# transponder-11_0_0.net
KiCad netlist of a schematic drawn in EAGLE
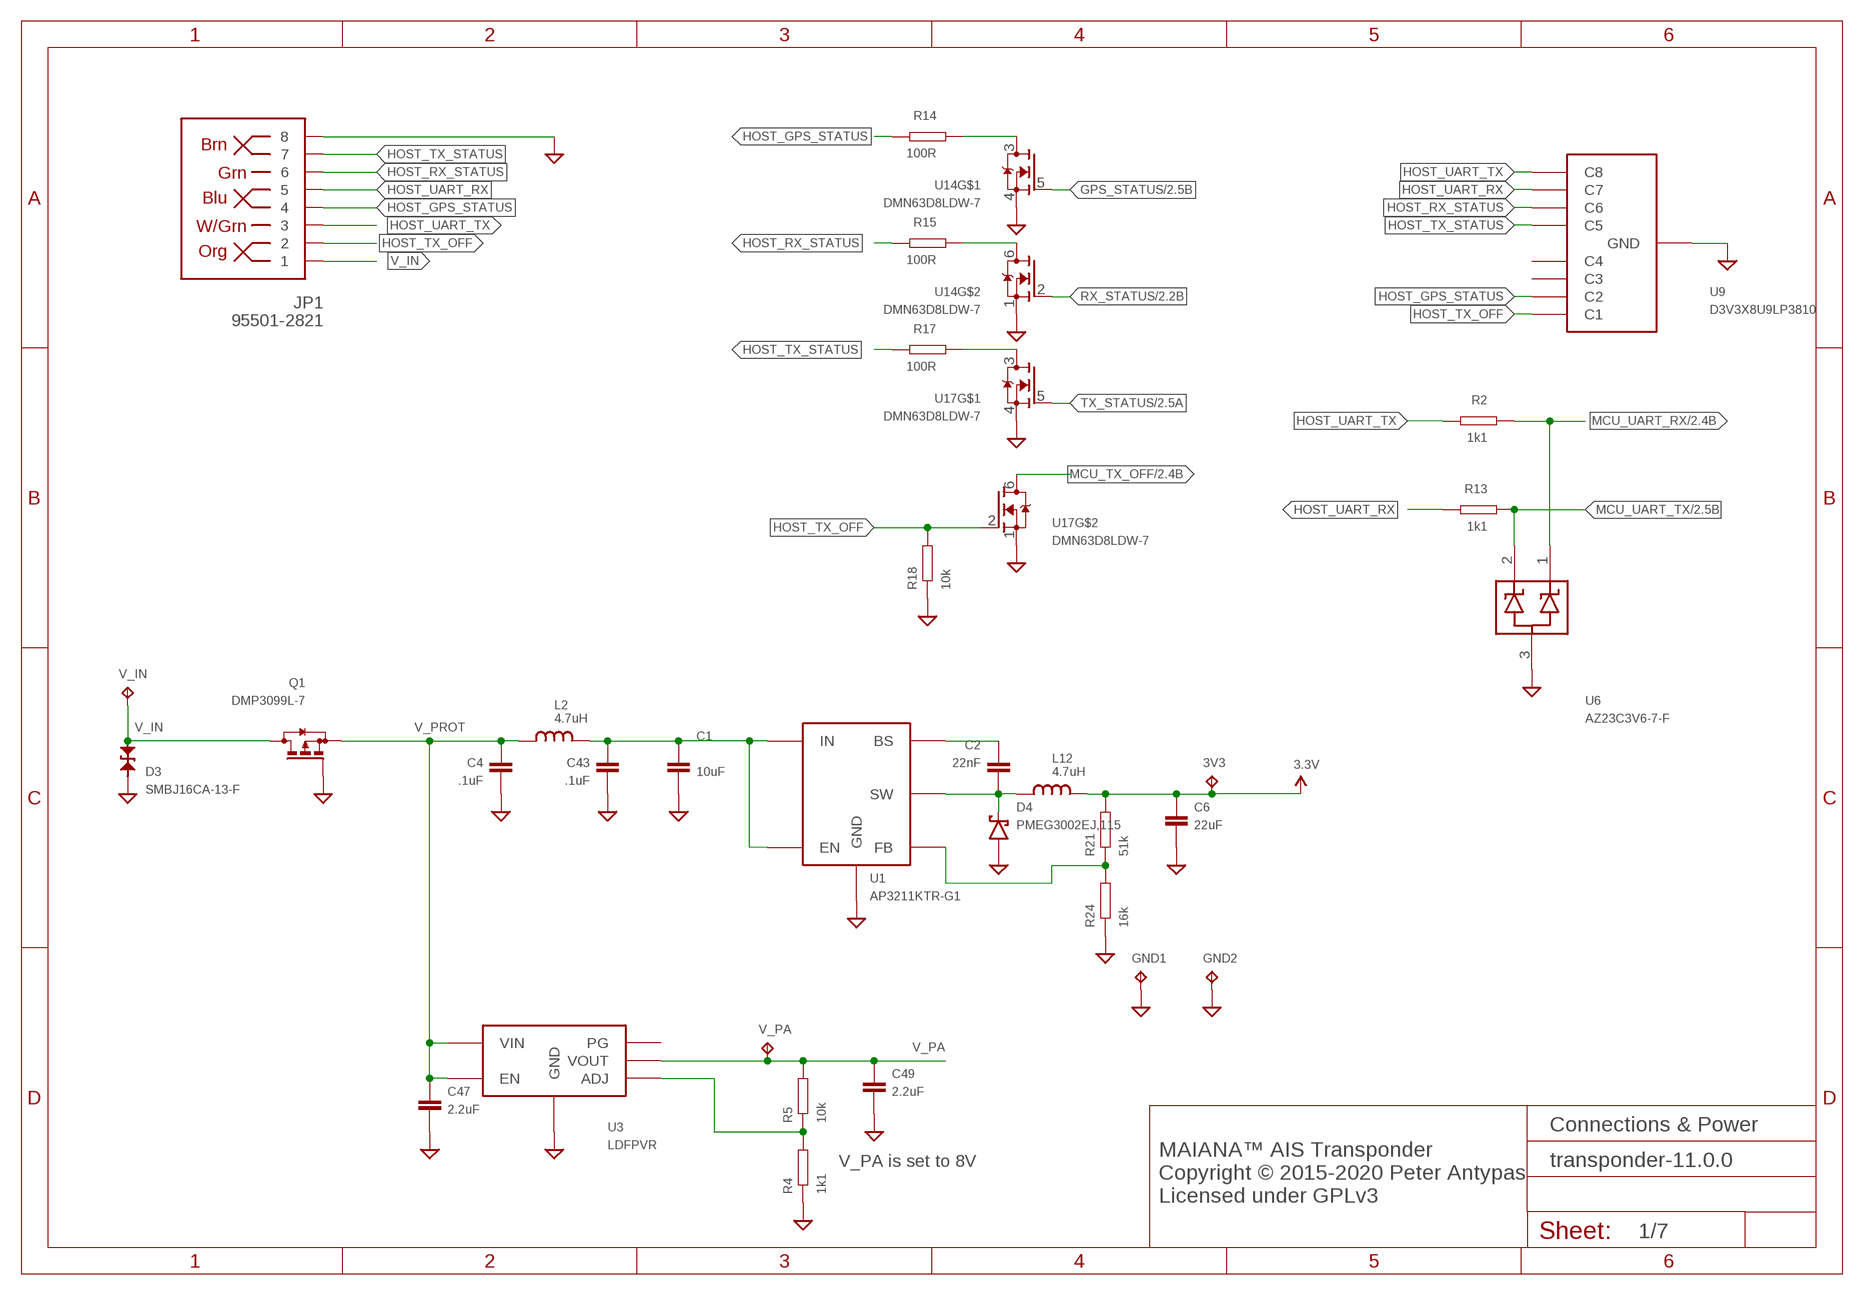
[diagram p0: schematic, sheet 1]
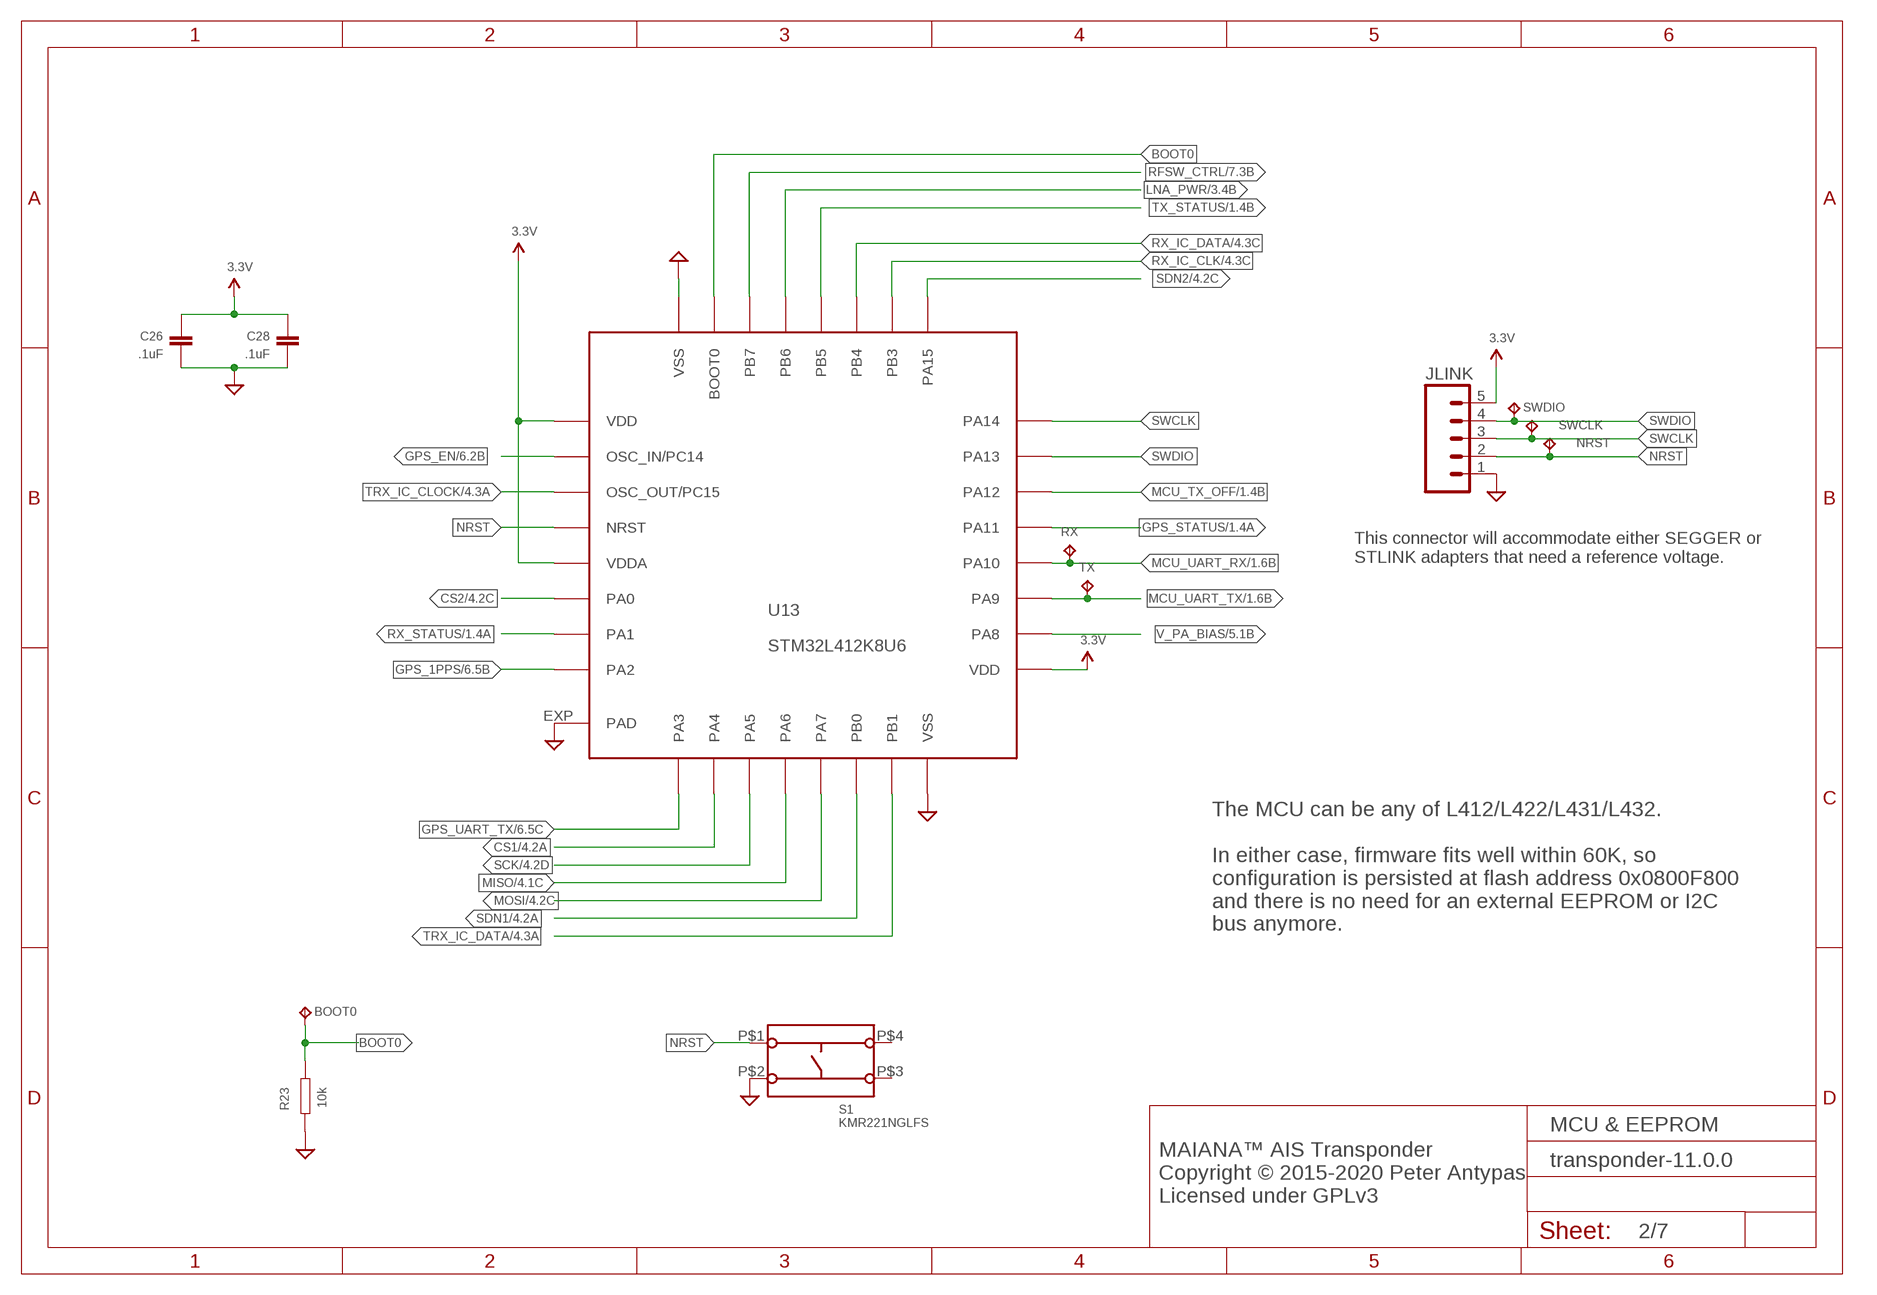
[diagram p1: schematic, sheet 2]
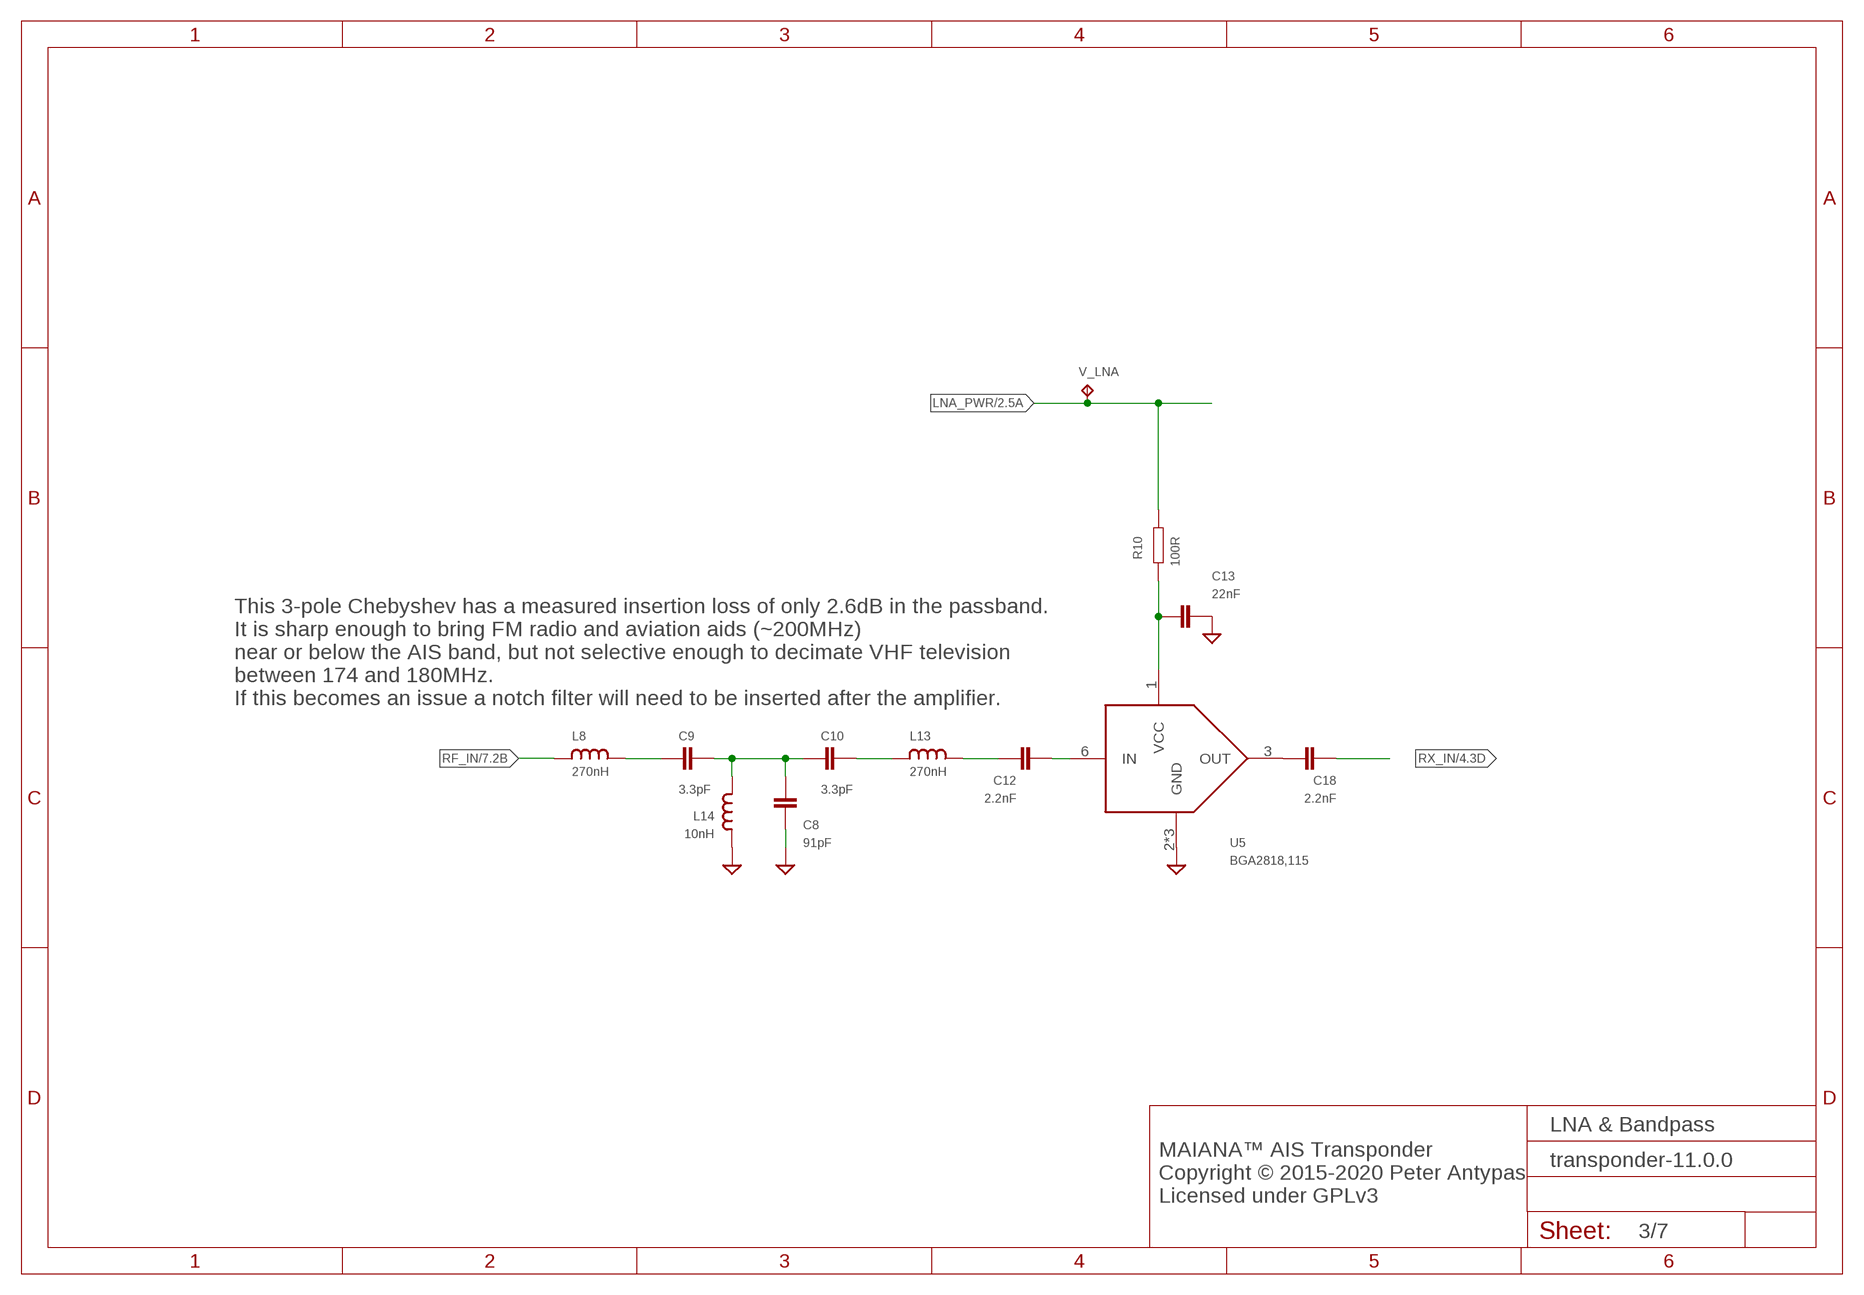
[diagram p2: schematic, sheet 3]
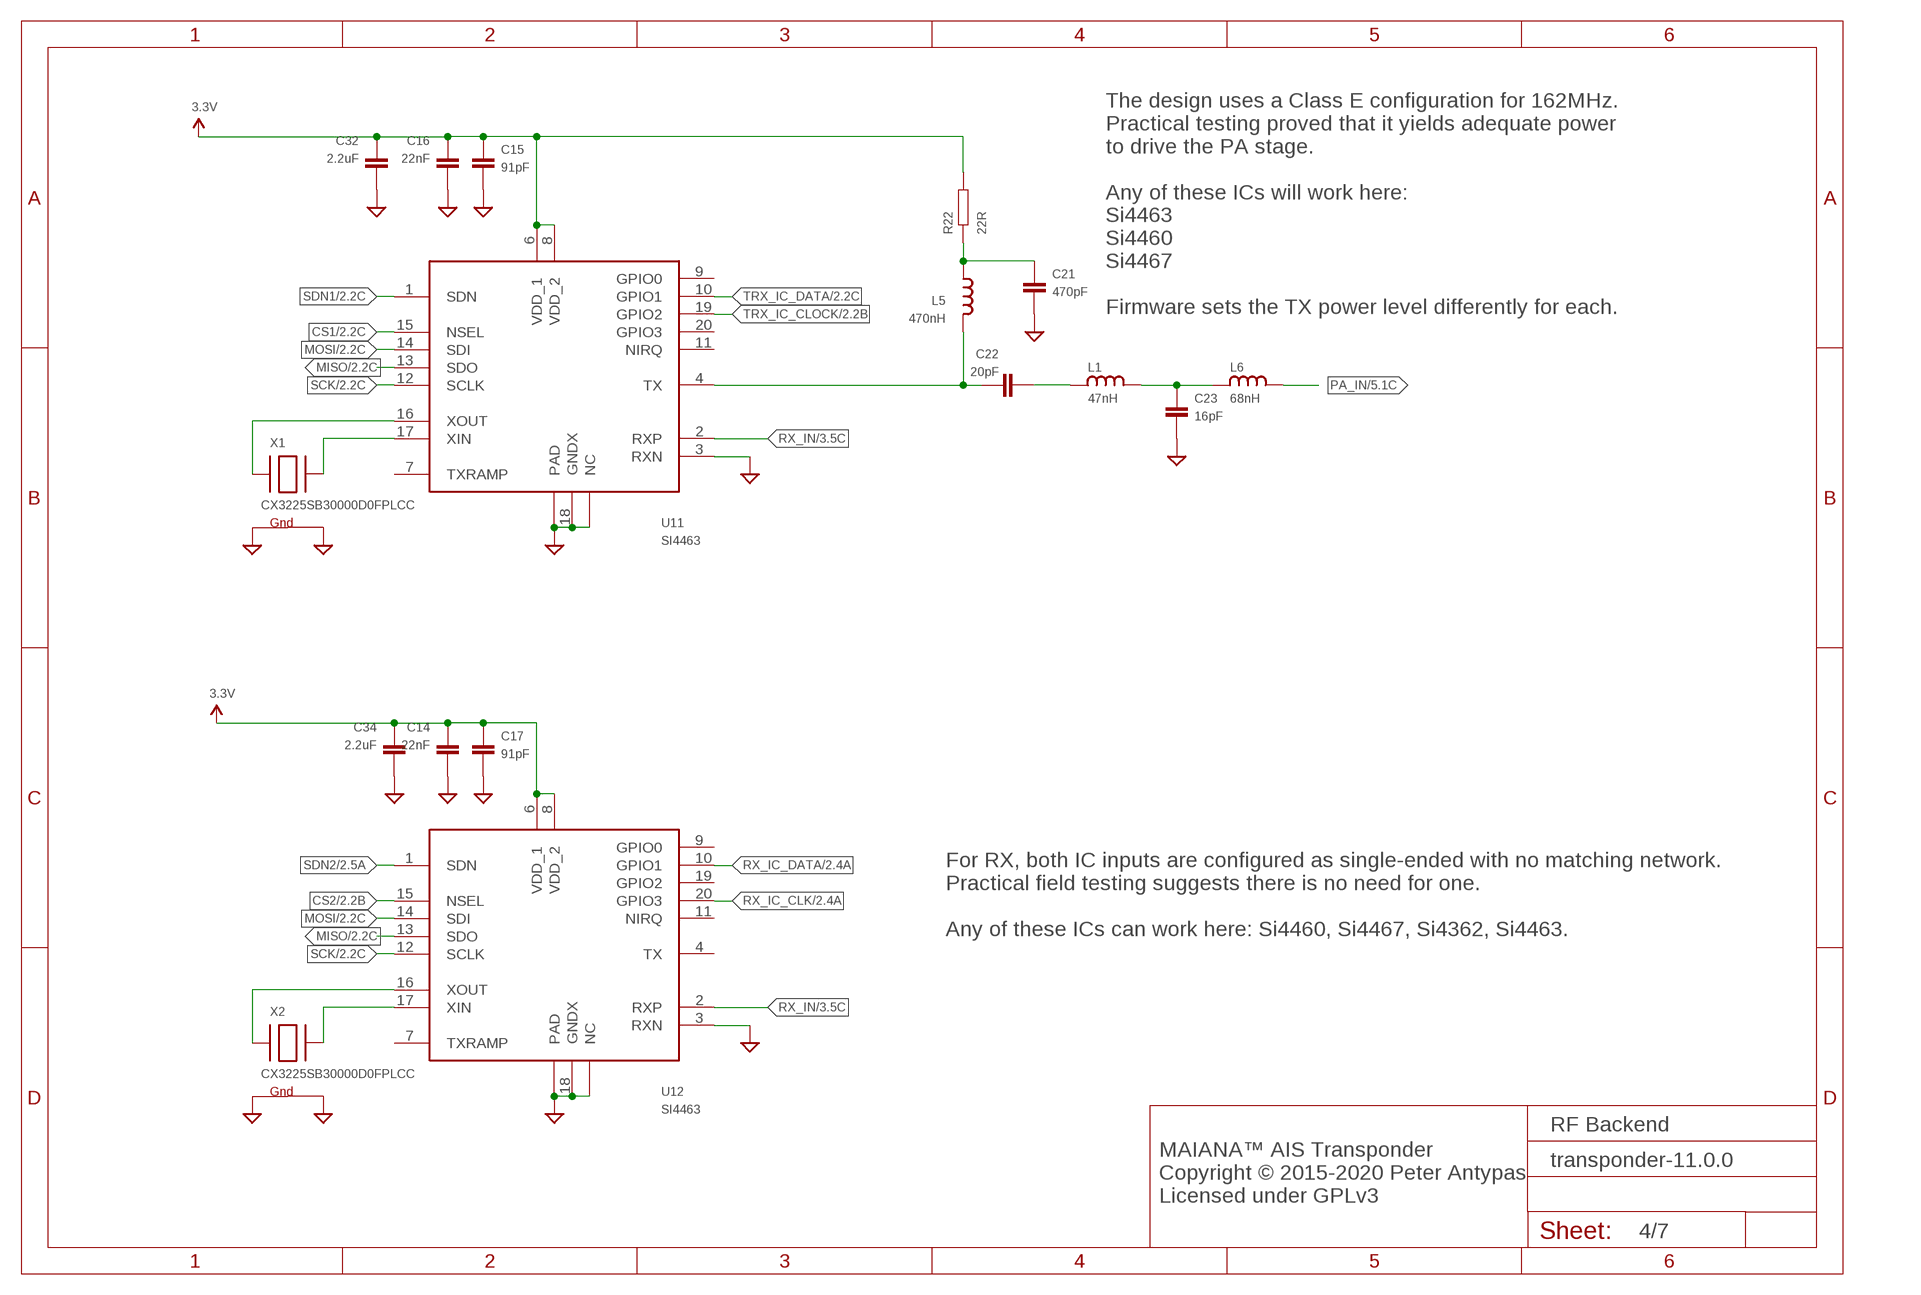
[diagram p3: schematic, sheet 4]
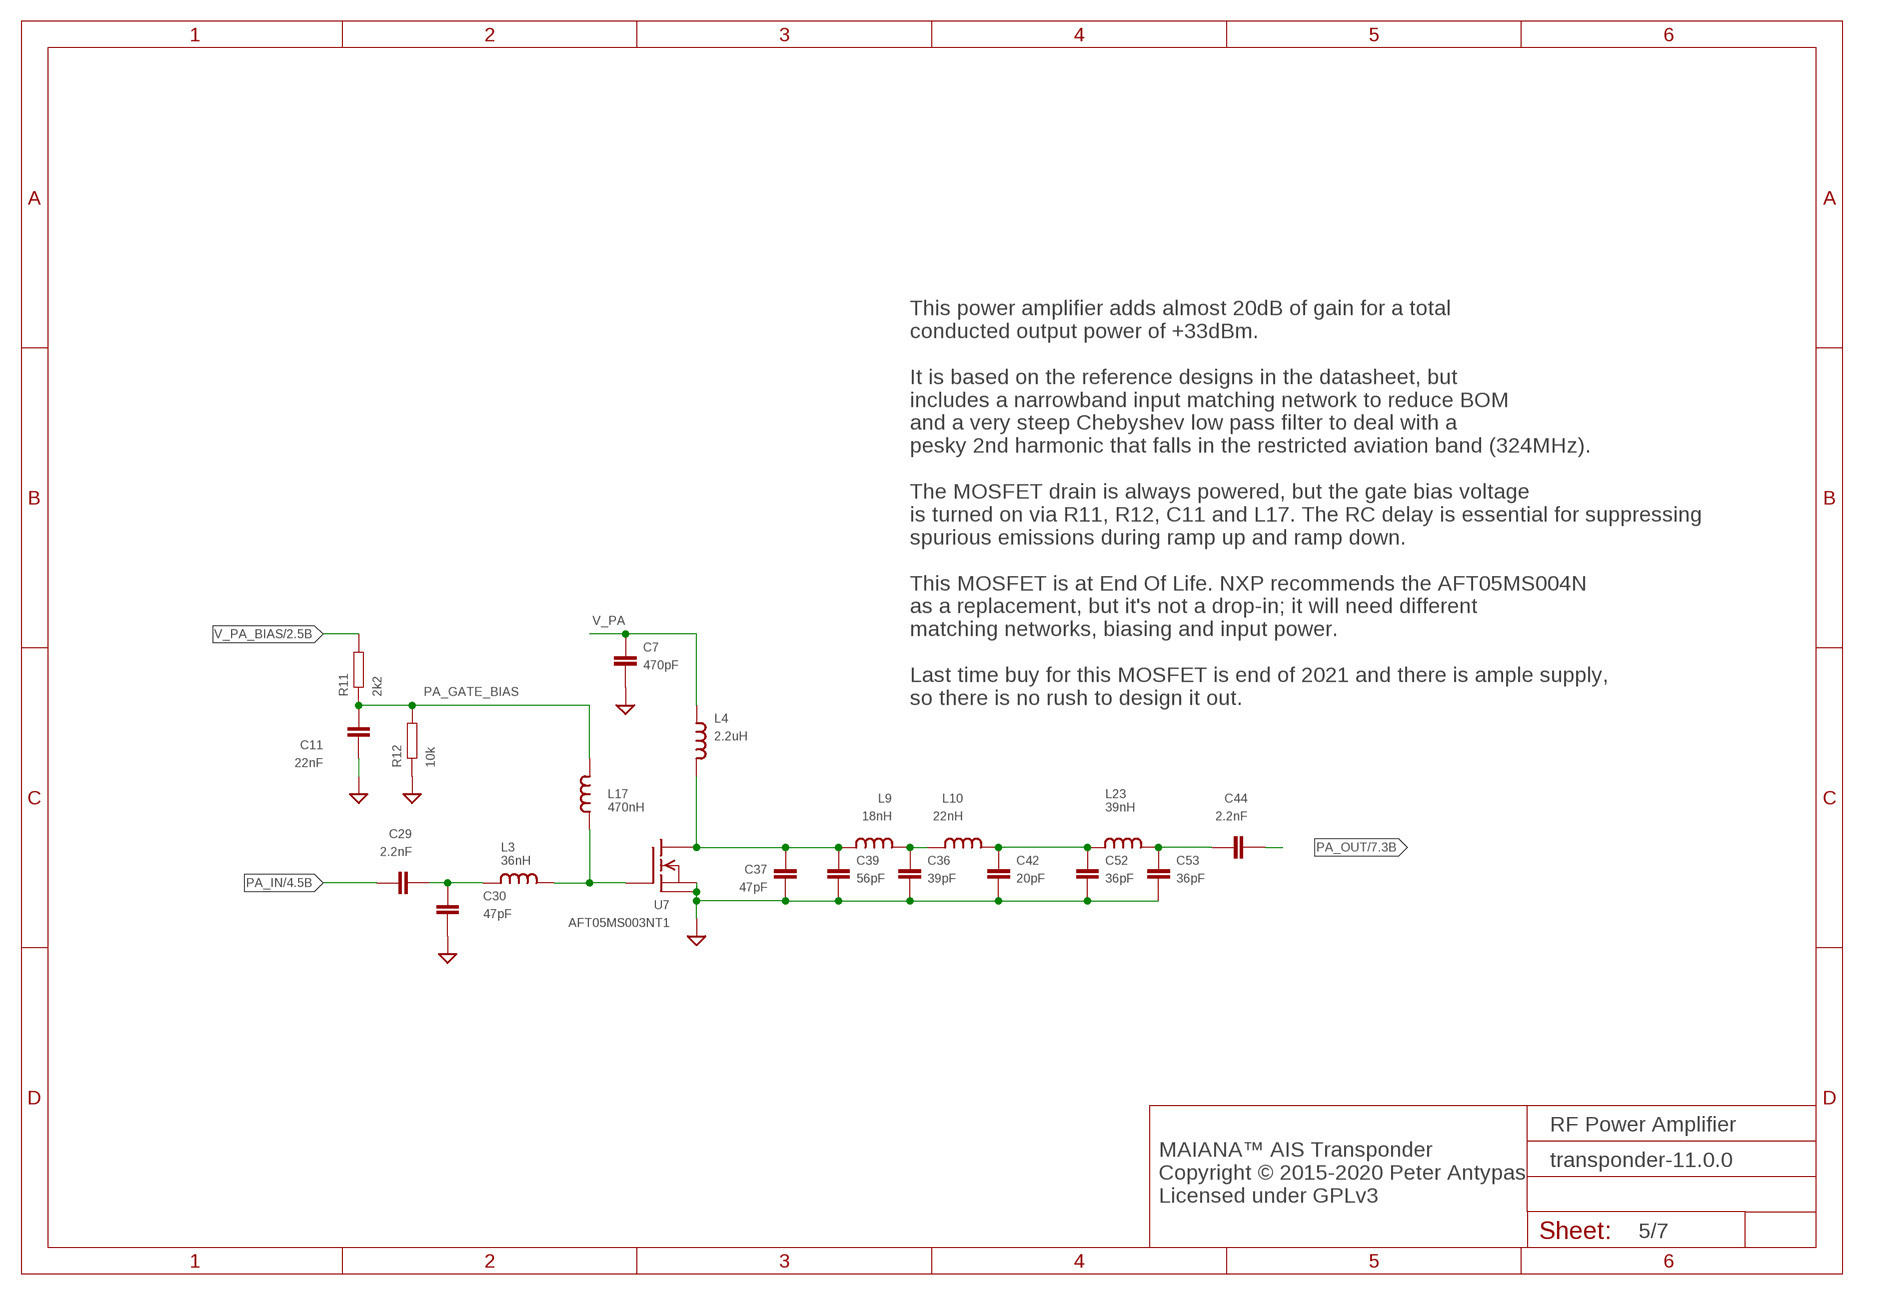
[diagram p4: schematic, sheet 5]
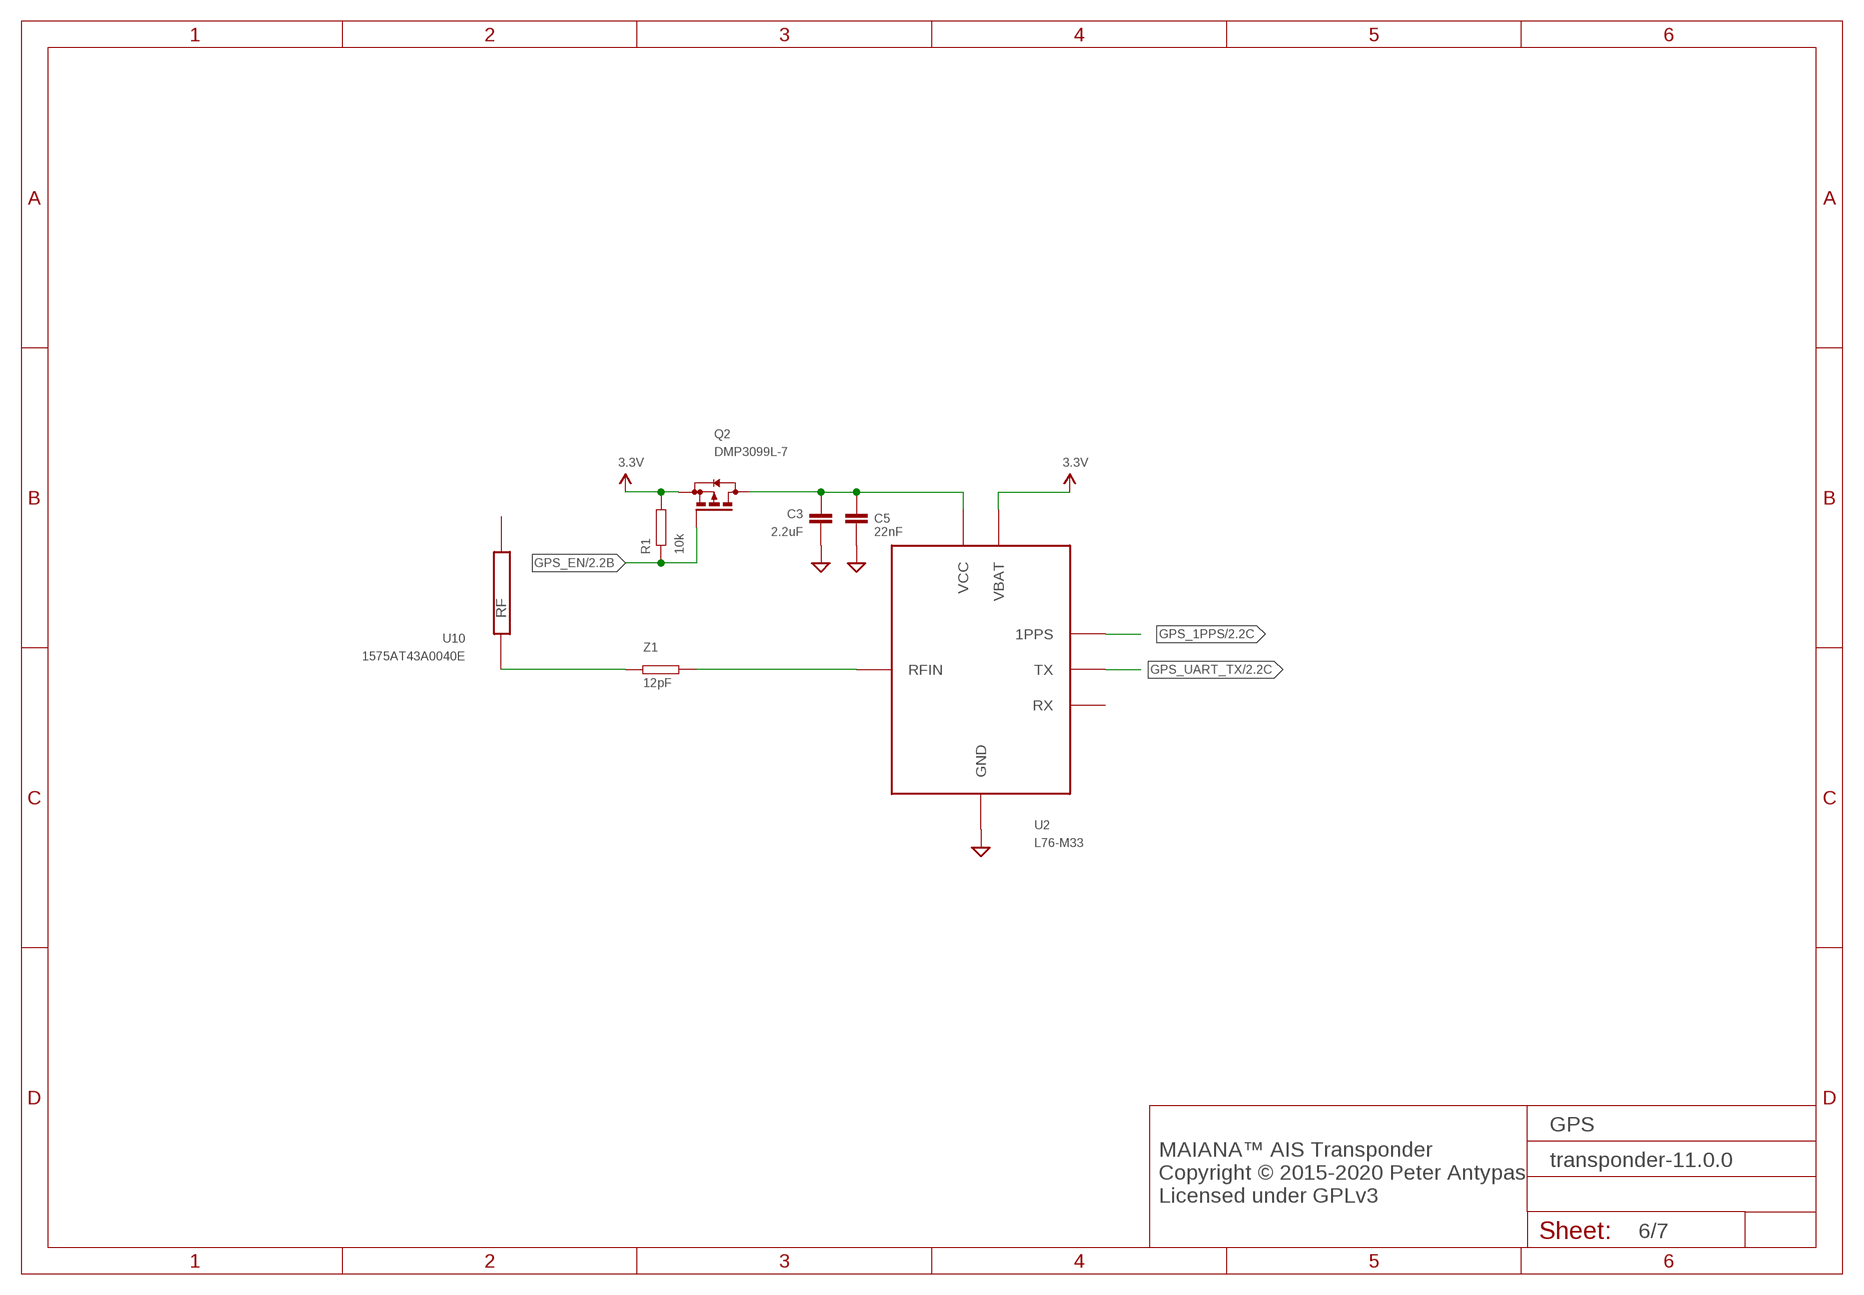
[diagram p5: schematic, sheet 6]
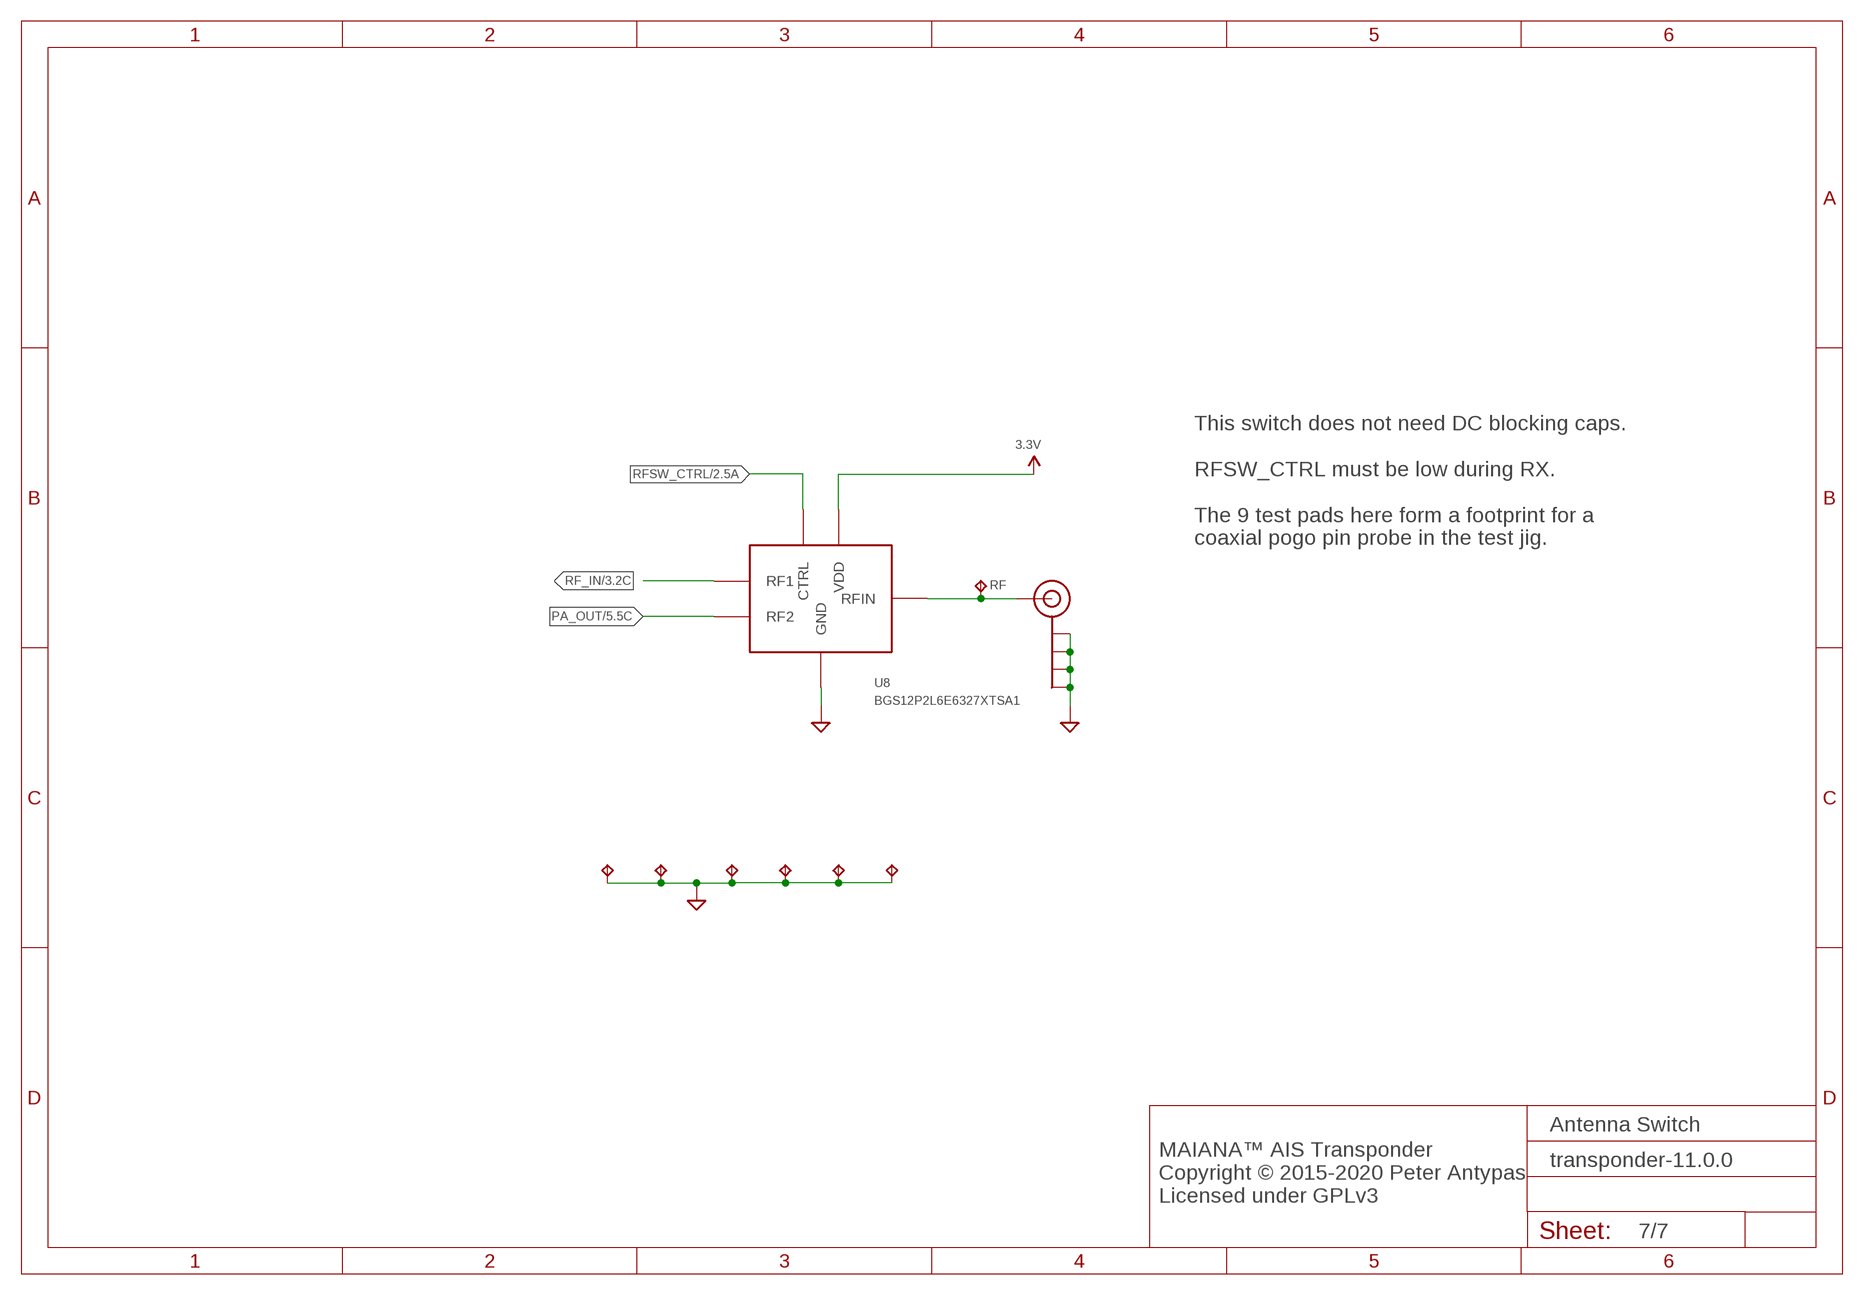
[diagram p6: schematic, sheet 7]

(export (version "E")
  (design (tool "Eeschema 10.0.6"))
  (components
    (comp (ref "C7")
      (value "470pF")
      (footprint "eagle-import:0603")
      (fields (field (name "PARTNO") "GRM1885C1H471JA01D"))
      (libsource (lib "eagle-import") (part "CAPACITOR0603"))
    )
    (comp (ref "C11")
      (value "22nF")
      (footprint "eagle-import:0603")
      (fields (field (name "PARTNO") "GRM188R71E223KA01D"))
      (libsource (lib "eagle-import") (part "CAPACITOR0603"))
    )
    (comp (ref "C29")
      (value "2.2nF")
      (footprint "eagle-import:0603")
      (fields (field (name "PARTNO") "GRM1885C1H222JA01J"))
      (libsource (lib "eagle-import") (part "CAPACITOR0603"))
    )
    (comp (ref "C30")
      (value "47pF")
      (footprint "eagle-import:0603")
      (fields (field (name "PARTNO") "GRM1885C1H470JA01J"))
      (libsource (lib "eagle-import") (part "CAPACITOR0603"))
    )
    (comp (ref "C36")
      (value "39pF")
      (footprint "eagle-import:0603")
      (fields (field (name "PARTNO") "GRM1885C1H390JA01D"))
      (libsource (lib "eagle-import") (part "CAPACITOR0603"))
    )
    (comp (ref "C37")
      (value "47pF")
      (footprint "eagle-import:0603")
      (fields (field (name "PARTNO") "GRM1885C1H470JA01J"))
      (libsource (lib "eagle-import") (part "CAPACITOR0603"))
    )
    (comp (ref "C39")
      (value "56pF")
      (footprint "eagle-import:0603")
      (fields (field (name "PARTNO") "GRM1885C1H560JA01D"))
      (libsource (lib "eagle-import") (part "CAPACITOR0603"))
    )
    (comp (ref "C42")
      (value "20pF")
      (footprint "eagle-import:0603")
      (fields (field (name "PARTNO") "GRM1885C1H200JA01D"))
      (libsource (lib "eagle-import") (part "CAPACITOR0603"))
    )
    (comp (ref "C44")
      (value "2.2nF")
      (footprint "eagle-import:0603")
      (fields (field (name "PARTNO") "GRM1885C1H222JA01J"))
      (libsource (lib "eagle-import") (part "CAPACITOR0603"))
    )
    (comp (ref "C52")
      (value "36pF")
      (footprint "eagle-import:0603")
      (fields (field (name "PARTNO") "06035A360JAT2A"))
      (libsource (lib "eagle-import") (part "CAPACITOR0603"))
    )
    (comp (ref "C53")
      (value "36pF")
      (footprint "eagle-import:0603")
      (fields (field (name "PARTNO") "06035A360JAT2A"))
      (libsource (lib "eagle-import") (part "CAPACITOR0603"))
    )
    (comp (ref "L3")
      (value "36nH")
      (footprint "eagle-import:0603")
      (fields (field (name "PARTNO") "LQW18AN36NG00D"))
      (libsource (lib "eagle-import") (part "INDUCTOR0603"))
    )
    (comp (ref "L4")
      (value "2.2uH")
      (footprint "eagle-import:0805")
      (fields (field (name "PARTNO") "BRC2012T2R2MD"))
      (libsource (lib "eagle-import") (part "INDUCTOR0805"))
    )
    (comp (ref "L9")
      (value "18nH")
      (footprint "eagle-import:0603")
      (fields (field (name "PARTNO") "LQW18AN18NG00D"))
      (libsource (lib "eagle-import") (part "INDUCTOR0603"))
    )
    (comp (ref "L10")
      (value "22nH")
      (footprint "eagle-import:0603")
      (fields (field (name "PARTNO") "LQW18AN22NJ00D"))
      (libsource (lib "eagle-import") (part "INDUCTOR0603"))
    )
    (comp (ref "L17")
      (value "470nH")
      (footprint "eagle-import:0603")
      (fields (field (name "PARTNO") "HK1608R47J-T"))
      (libsource (lib "eagle-import") (part "INDUCTOR0603"))
    )
    (comp (ref "L23")
      (value "39nH")
      (footprint "eagle-import:0603")
      (fields (field (name "PARTNO") "LQW18AN39NG00D"))
      (libsource (lib "eagle-import") (part "INDUCTOR0603"))
    )
    (comp (ref "R11")
      (value "2k2")
      (footprint "eagle-import:0603")
      (fields (field (name "PARTNO") "RC0603FR-072K2L"))
      (libsource (lib "eagle-import") (part "RESISTOR0603"))
    )
    (comp (ref "R12")
      (value "10k")
      (footprint "eagle-import:0603")
      (fields (field (name "PARTNO") "RC0603JR-0710KL"))
      (libsource (lib "eagle-import") (part "RESISTOR0603"))
    )
    (comp (ref "U7")
      (value "AFT05MS003NT1")
      (footprint "eagle-import:SOT-89")
      (libsource (lib "eagle-import") (part "AFT0SMS003N"))
    )
    (comp (ref "J$1")
      (value "SMA_EDGE")
      (footprint "eagle-import:SMA-EDGE")
      (libsource (lib "eagle-import") (part "SMA_EDGE"))
    )
    (comp (ref "RF")
      (value "TPTP10R")
      (footprint "eagle-import:TP10R")
      (libsource (lib "eagle-import") (part "TPTP10R"))
    )
    (comp (ref "SWDIO1")
      (value "TPTP12R")
      (footprint "eagle-import:TP12R")
      (libsource (lib "eagle-import") (part "TPTP12R"))
    )
    (comp (ref "SWDIO2")
      (value "TPTP12R")
      (footprint "eagle-import:TP12R")
      (libsource (lib "eagle-import") (part "TPTP12R"))
    )
    (comp (ref "SWDIO3")
      (value "TPTP12R")
      (footprint "eagle-import:TP12R")
      (libsource (lib "eagle-import") (part "TPTP12R"))
    )
    (comp (ref "SWDIO4")
      (value "TPTP12R")
      (footprint "eagle-import:TP12R")
      (libsource (lib "eagle-import") (part "TPTP12R"))
    )
    (comp (ref "SWDIO5")
      (value "TPTP12R")
      (footprint "eagle-import:TP12R")
      (libsource (lib "eagle-import") (part "TPTP12R"))
    )
    (comp (ref "SWDIO6")
      (value "TPTP12R")
      (footprint "eagle-import:TP12R")
      (libsource (lib "eagle-import") (part "TPTP12R"))
    )
    (comp (ref "U8")
      (value "BGS12P2L6E6327XTSA1")
      (footprint "eagle-import:PSON50P145X100X50-6N")
      (fields (field (name "PARTNO") "BGS12PL6") (field (name "PARTNO_1") "‎BGS12P2L6E6327XTSA1‎"))
      (libsource (lib "eagle-import") (part "BGS12PL6"))
    )
    (comp (ref "C3")
      (value "2.2uF")
      (footprint "eagle-import:0603")
      (fields (field (name "PARTNO") "EMK107BJ225KA-T"))
      (libsource (lib "eagle-import") (part "CAPACITOR0603"))
    )
    (comp (ref "C5")
      (value "22nF")
      (footprint "eagle-import:0603")
      (fields (field (name "PARTNO") "GRM188R71E223KA01D"))
      (libsource (lib "eagle-import") (part "CAPACITOR0603"))
    )
    (comp (ref "Q2")
      (value "DMP3099L-7")
      (footprint "eagle-import:SOT23")
      (libsource (lib "eagle-import") (part "BSS84"))
    )
    (comp (ref "R1")
      (value "10k")
      (footprint "eagle-import:0603")
      (fields (field (name "PARTNO") "RC0603JR-0710KL"))
      (libsource (lib "eagle-import") (part "RESISTOR0603"))
    )
    (comp (ref "U2")
      (value "L76-M33")
      (footprint "eagle-import:GPS_MODULE")
      (fields (field (name "PARTNO") "L70B-M39"))
      (libsource (lib "eagle-import") (part "L70"))
    )
    (comp (ref "U10")
      (value "1575AT43A0040E")
      (footprint "eagle-import:1575AT43A0040E")
      (libsource (lib "eagle-import") (part "1575AT43A0040E"))
    )
    (comp (ref "Z1")
      (value "12pF")
      (footprint "eagle-import:0603")
      (fields (field (name "PARTNO") "‎GRM1885C1H120GA01D‎"))
      (libsource (lib "eagle-import") (part "RESISTOR0603"))
    )
    (comp (ref "3V3")
      (value "TPTP12R")
      (footprint "eagle-import:TP12R")
      (libsource (lib "eagle-import") (part "TPTP12R"))
    )
    (comp (ref "C1")
      (value "10uF")
      (footprint "eagle-import:0805")
      (fields (field (name "PARTNO") "EMK212ABJ106KG-T"))
      (libsource (lib "eagle-import") (part "CAPACITOR0805"))
    )
    (comp (ref "C2")
      (value "22nF")
      (footprint "eagle-import:0603")
      (fields (field (name "PARTNO") "GRM188R71E223KA01D"))
      (libsource (lib "eagle-import") (part "CAPACITOR0603"))
    )
    (comp (ref "C4")
      (value ".1uF")
      (footprint "eagle-import:0603")
      (fields (field (name "PARTNO") "EMK107B7104KAHT"))
      (libsource (lib "eagle-import") (part "CAPACITOR0603"))
    )
    (comp (ref "C6")
      (value "22uF")
      (footprint "eagle-import:0805")
      (libsource (lib "eagle-import") (part "CAPACITOR0805"))
    )
    (comp (ref "C43")
      (value ".1uF")
      (footprint "eagle-import:0603")
      (fields (field (name "PARTNO") "EMK107B7104KAHT"))
      (libsource (lib "eagle-import") (part "CAPACITOR0603"))
    )
    (comp (ref "C47")
      (value "2.2uF")
      (footprint "eagle-import:0603")
      (fields (field (name "PARTNO") "EMK107BJ225KA-T"))
      (libsource (lib "eagle-import") (part "CAPACITOR0603"))
    )
    (comp (ref "C49")
      (value "2.2uF")
      (footprint "eagle-import:0603")
      (fields (field (name "PARTNO") "EMK107BJ225KA-T"))
      (libsource (lib "eagle-import") (part "CAPACITOR0603"))
    )
    (comp (ref "D3")
      (value "SMBJ16CA-13-F")
      (footprint "eagle-import:SMB-BIDIR")
      (fields (field (name "PARTNO") "SMBJ16CA-13-F"))
      (libsource (lib "eagle-import") (part "DIODE-TVS-BIDIRSMB"))
    )
    (comp (ref "D4")
      (value "PMEG3002EJ,115")
      (footprint "eagle-import:SOD323")
      (fields (field (name "PARTNO") "NSR0240HT1G"))
      (libsource (lib "eagle-import") (part "DIODE-SCHOTTKYSOD323"))
    )
    (comp (ref "GND1")
      (value "TPTP12R")
      (footprint "eagle-import:TP12R")
      (libsource (lib "eagle-import") (part "TPTP12R"))
    )
    (comp (ref "GND2")
      (value "TPTP12R")
      (footprint "eagle-import:TP12R")
      (libsource (lib "eagle-import") (part "TPTP12R"))
    )
    (comp (ref "JP1")
      (value "95501-2821")
      (footprint "eagle-import:RJ45-8")
      (libsource (lib "eagle-import") (part "RJ45-8PTH"))
    )
    (comp (ref "L2")
      (value "4.7uH")
      (footprint "eagle-import:0805")
      (fields (field (name "PARTNO") "MLZ2012M4R7WT000"))
      (libsource (lib "eagle-import") (part "INDUCTOR0805"))
    )
    (comp (ref "L12")
      (value "4.7uH")
      (footprint "eagle-import:0805")
      (fields (field (name "PARTNO") "MLZ2012M4R7WT000"))
      (libsource (lib "eagle-import") (part "INDUCTOR0805"))
    )
    (comp (ref "Q1")
      (value "DMP3099L-7")
      (footprint "eagle-import:SOT23")
      (libsource (lib "eagle-import") (part "BSS84"))
    )
    (comp (ref "R2")
      (value "1k1")
      (footprint "eagle-import:0603")
      (fields (field (name "PARTNO") "RC0603JR-071K1L"))
      (libsource (lib "eagle-import") (part "RESISTOR0603"))
    )
    (comp (ref "R4")
      (value "1k1")
      (footprint "eagle-import:0603")
      (fields (field (name "PARTNO") "RC0603JR-071K1L"))
      (libsource (lib "eagle-import") (part "RESISTOR0603"))
    )
    (comp (ref "R5")
      (value "10k")
      (footprint "eagle-import:0603")
      (fields (field (name "PARTNO") "RC0603JR-0710KL"))
      (libsource (lib "eagle-import") (part "RESISTOR0603"))
    )
    (comp (ref "R13")
      (value "1k1")
      (footprint "eagle-import:0603")
      (fields (field (name "PARTNO") "RC0603JR-071K1L"))
      (libsource (lib "eagle-import") (part "RESISTOR0603"))
    )
    (comp (ref "R14")
      (value "100R")
      (footprint "eagle-import:0603")
      (fields (field (name "PARTNO") "RC0603JR-07100RL"))
      (libsource (lib "eagle-import") (part "RESISTOR0603"))
    )
    (comp (ref "R15")
      (value "100R")
      (footprint "eagle-import:0603")
      (fields (field (name "PARTNO") "RC0603JR-07100RL"))
      (libsource (lib "eagle-import") (part "RESISTOR0603"))
    )
    (comp (ref "R17")
      (value "100R")
      (footprint "eagle-import:0603")
      (fields (field (name "PARTNO") "RC0603JR-070RL"))
      (libsource (lib "eagle-import") (part "RESISTOR0603"))
    )
    (comp (ref "R18")
      (value "10k")
      (footprint "eagle-import:0603")
      (fields (field (name "PARTNO") "RC0603JR-0710KL"))
      (libsource (lib "eagle-import") (part "RESISTOR0603"))
    )
    (comp (ref "R21")
      (value "51k")
      (footprint "eagle-import:0603")
      (fields (field (name "PARTNO") "RC0603JR-0751KL"))
      (libsource (lib "eagle-import") (part "RESISTOR0603"))
    )
    (comp (ref "R24")
      (value "16k")
      (footprint "eagle-import:0603")
      (fields (field (name "PARTNO") "RC0603FR-1016KL"))
      (libsource (lib "eagle-import") (part "RESISTOR0603"))
    )
    (comp (ref "U1")
      (value "AP3211KTR-G1")
      (footprint "eagle-import:SOT23-6")
      (libsource (lib "eagle-import") (part "AP3211"))
    )
    (comp (ref "U3")
      (value "LDFPVR")
      (footprint "eagle-import:DFN6-2X2")
      (fields (field (name "PARTNO") "LDFPUR"))
      (libsource (lib "eagle-import") (part "LDFPVR"))
    )
    (comp (ref "U6")
      (value "AZ23C3V6-7-F")
      (footprint "eagle-import:SOT-23")
      (libsource (lib "eagle-import") (part "AZ23C3V6-7-F"))
    )
    (comp (ref "U9")
      (value "D3V3X8U9LP3810")
      (footprint "eagle-import:U-DFN3810-9(B)")
      (libsource (lib "eagle-import") (part "D3V3X8U9LP3810"))
    )
    (comp (ref "U14")
      (value "DMN63D8LDW-7")
      (footprint "eagle-import:SOT363")
      (fields (field (name "PARTNO") "DMN63D8LDW-7"))
      (libsource (lib "eagle-import") (part "DMN63D8LDW"))
    )
    (comp (ref "U17")
      (value "DMN63D8LDW-7")
      (footprint "eagle-import:SOT363")
      (fields (field (name "PARTNO") "DMN63D8LDW-7"))
      (libsource (lib "eagle-import") (part "DMN63D8LDW"))
    )
    (comp (ref "V_IN")
      (value "TPTP12R")
      (footprint "eagle-import:TP12R")
      (libsource (lib "eagle-import") (part "TPTP12R"))
    )
    (comp (ref "V_PA")
      (value "TPTP12R")
      (footprint "eagle-import:TP12R")
      (libsource (lib "eagle-import") (part "TPTP12R"))
    )
    (comp (ref "C14")
      (value "22nF")
      (footprint "eagle-import:0603")
      (fields (field (name "PARTNO") "GRM188R71E223KA01D"))
      (libsource (lib "eagle-import") (part "CAPACITOR0603"))
    )
    (comp (ref "C15")
      (value "91pF")
      (footprint "eagle-import:0603")
      (fields (field (name "PARTNO") "GRM1885C2A910JA01D"))
      (libsource (lib "eagle-import") (part "CAPACITOR0603"))
    )
    (comp (ref "C16")
      (value "22nF")
      (footprint "eagle-import:0603")
      (fields (field (name "PARTNO") "GRM188R71E223KA01D"))
      (libsource (lib "eagle-import") (part "CAPACITOR0603"))
    )
    (comp (ref "C17")
      (value "91pF")
      (footprint "eagle-import:0603")
      (fields (field (name "PARTNO") "GRM1885C2A910JA01D"))
      (libsource (lib "eagle-import") (part "CAPACITOR0603"))
    )
    (comp (ref "C21")
      (value "470pF")
      (footprint "eagle-import:0603")
      (fields (field (name "PARTNO") "GRM1885C1H471JA01D"))
      (libsource (lib "eagle-import") (part "CAPACITOR0603"))
    )
    (comp (ref "C22")
      (value "20pF")
      (footprint "eagle-import:0603")
      (fields (field (name "PARTNO") "GRM1885C1H200JA01D"))
      (libsource (lib "eagle-import") (part "CAPACITOR0603"))
    )
    (comp (ref "C23")
      (value "16pF")
      (footprint "eagle-import:0603")
      (fields (field (name "PARTNO") "GCM1885C2A160JA16D"))
      (libsource (lib "eagle-import") (part "CAPACITOR0603"))
    )
    (comp (ref "C32")
      (value "2.2uF")
      (footprint "eagle-import:0603")
      (fields (field (name "PARTNO") "EMK107BJ225KA-T"))
      (libsource (lib "eagle-import") (part "CAPACITOR0603"))
    )
    (comp (ref "C34")
      (value "2.2uF")
      (footprint "eagle-import:0603")
      (fields (field (name "PARTNO") "EMK107BJ225KA-T"))
      (libsource (lib "eagle-import") (part "CAPACITOR0603"))
    )
    (comp (ref "L1")
      (value "47nH")
      (footprint "eagle-import:0603")
      (fields (field (name "PARTNO") "LQW18AN47NG00D"))
      (libsource (lib "eagle-import") (part "INDUCTOR0603"))
    )
    (comp (ref "L5")
      (value "470nH")
      (footprint "eagle-import:0603")
      (fields (field (name "PARTNO") "HK1608R47J-T"))
      (libsource (lib "eagle-import") (part "INDUCTOR0603"))
    )
    (comp (ref "L6")
      (value "68nH")
      (footprint "eagle-import:0603")
      (libsource (lib "eagle-import") (part "INDUCTOR0603"))
    )
    (comp (ref "R22")
      (value "22R")
      (footprint "eagle-import:0603")
      (fields (field (name "PARTNO") "RC0603JR-0722RL"))
      (libsource (lib "eagle-import") (part "RESISTOR0603"))
    )
    (comp (ref "U11")
      (value "SI4463")
      (footprint "eagle-import:SI4463")
      (fields (field (name "PARTNO") "SI4463-C2A-GMR"))
      (libsource (lib "eagle-import") (part "SI4463"))
    )
    (comp (ref "U12")
      (value "SI4463")
      (footprint "eagle-import:SI4463")
      (fields (field (name "PARTNO") "SI4463-C2A-GMR"))
      (libsource (lib "eagle-import") (part "SI4463"))
    )
    (comp (ref "X1")
      (value "CX3225SB30000D0FPLCC")
      (footprint "eagle-import:NX3225")
      (libsource (lib "eagle-import") (part "XTAL-4-3225"))
    )
    (comp (ref "X2")
      (value "CX3225SB30000D0FPLCC")
      (footprint "eagle-import:NX3225")
      (libsource (lib "eagle-import") (part "XTAL-4-3225"))
    )
    (comp (ref "C8")
      (value "91pF")
      (footprint "eagle-import:0603")
      (fields (field (name "PARTNO") "GRM1885C2A910JA01D"))
      (libsource (lib "eagle-import") (part "CAPACITOR0603"))
    )
    (comp (ref "C9")
      (value "3.3pF")
      (footprint "eagle-import:0603")
      (fields (field (name "PARTNO") "GRM1885C1H3R3BA01D"))
      (libsource (lib "eagle-import") (part "CAPACITOR0603"))
    )
    (comp (ref "C10")
      (value "3.3pF")
      (footprint "eagle-import:0603")
      (fields (field (name "PARTNO") "GRM1885C1H3R3BA01D"))
      (libsource (lib "eagle-import") (part "CAPACITOR0603"))
    )
    (comp (ref "C12")
      (value "2.2nF")
      (footprint "eagle-import:0603")
      (fields (field (name "PARTNO") "GRM1885C1H222JA01J"))
      (libsource (lib "eagle-import") (part "CAPACITOR0603"))
    )
    (comp (ref "C13")
      (value "22nF")
      (footprint "eagle-import:0603")
      (fields (field (name "PARTNO") "GRM188R71E223KA01D"))
      (libsource (lib "eagle-import") (part "CAPACITOR0603"))
    )
    (comp (ref "C18")
      (value "2.2nF")
      (footprint "eagle-import:0603")
      (fields (field (name "PARTNO") "GRM1885C1H222JA01J"))
      (libsource (lib "eagle-import") (part "CAPACITOR0603"))
    )
    (comp (ref "L8")
      (value "270nH")
      (footprint "eagle-import:0603")
      (fields (field (name "PARTNO") "LQW18ANR27J00D"))
      (libsource (lib "eagle-import") (part "INDUCTOR0603"))
    )
    (comp (ref "L13")
      (value "270nH")
      (footprint "eagle-import:0603")
      (fields (field (name "PARTNO") "LQW18ANR27J00D"))
      (libsource (lib "eagle-import") (part "INDUCTOR0603"))
    )
    (comp (ref "L14")
      (value "10nH")
      (footprint "eagle-import:0603")
      (fields (field (name "PARTNO") "LQW18AN10NG00D"))
      (libsource (lib "eagle-import") (part "INDUCTOR0603"))
    )
    (comp (ref "R10")
      (value "100R")
      (footprint "eagle-import:0603")
      (fields (field (name "PARTNO") "RC0603JR-07100RL"))
      (libsource (lib "eagle-import") (part "RESISTOR0603"))
    )
    (comp (ref "U5")
      (value "BGA2818,115")
      (footprint "eagle-import:SOT363")
      (libsource (lib "eagle-import") (part "BGA2870"))
    )
    (comp (ref "V_LNA")
      (value "TPTP12R")
      (footprint "eagle-import:TP12R")
      (libsource (lib "eagle-import") (part "TPTP12R"))
    )
    (comp (ref "BOOT0")
      (value "TPTP12R")
      (footprint "eagle-import:TP12R")
      (libsource (lib "eagle-import") (part "TPTP12R"))
    )
    (comp (ref "C26")
      (value ".1uF")
      (footprint "eagle-import:0603")
      (fields (field (name "PARTNO") "EMK107B7104KAHT"))
      (libsource (lib "eagle-import") (part "CAPACITOR0603"))
    )
    (comp (ref "C28")
      (value ".1uF")
      (footprint "eagle-import:0603")
      (fields (field (name "PARTNO") "EMK107B7104KAHT"))
      (libsource (lib "eagle-import") (part "CAPACITOR0603"))
    )
    (comp (ref "JLINK")
      (value "M05PTH")
      (footprint "eagle-import:1X05")
      (libsource (lib "eagle-import") (part "M05PTH"))
    )
    (comp (ref "NRST")
      (value "TPTP12R")
      (footprint "eagle-import:TP12R")
      (libsource (lib "eagle-import") (part "TPTP12R"))
    )
    (comp (ref "R23")
      (value "10k")
      (footprint "eagle-import:0603")
      (fields (field (name "PARTNO") "RC0603JR-0710KL"))
      (libsource (lib "eagle-import") (part "RESISTOR0603"))
    )
    (comp (ref "RX")
      (value "TPTP12R")
      (footprint "eagle-import:TP12R")
      (libsource (lib "eagle-import") (part "TPTP12R"))
    )
    (comp (ref "S1")
      (value "KMR221NGLFS")
      (footprint "eagle-import:KMR221NGLFS")
      (libsource (lib "eagle-import") (part "KMR221NGLFS"))
    )
    (comp (ref "SWCLK")
      (value "TPTP12R")
      (footprint "eagle-import:TP12R")
      (libsource (lib "eagle-import") (part "TPTP12R"))
    )
    (comp (ref "SWDIO")
      (value "TPTP12R")
      (footprint "eagle-import:TP12R")
      (libsource (lib "eagle-import") (part "TPTP12R"))
    )
    (comp (ref "TX")
      (value "TPTP12R")
      (footprint "eagle-import:TP12R")
      (libsource (lib "eagle-import") (part "TPTP12R"))
    )
    (comp (ref "U13")
      (value "STM32L412K8U6")
      (footprint "eagle-import:QFN32")
      (libsource (lib "eagle-import") (part "STM32L432KXXX"))
    )
  )
  (nets
    (net (code "1") (name "3.3V") (class "Default")
      (node (ref "3V3") (pin "TP") (pinfunction "TP_TP") (pintype "input"))
      (node (ref "C14") (pin "P$1") (pinfunction "1_P$1") (pintype "passive"))
      (node (ref "C15") (pin "P$1") (pinfunction "1_P$1") (pintype "passive"))
      (node (ref "C16") (pin "P$1") (pinfunction "1_P$1") (pintype "passive"))
      (node (ref "C17") (pin "P$1") (pinfunction "1_P$1") (pintype "passive"))
      (node (ref "C26") (pin "P$1") (pinfunction "1_P$1") (pintype "passive"))
      (node (ref "C28") (pin "P$1") (pinfunction "1_P$1") (pintype "passive"))
      (node (ref "C32") (pin "P$1") (pinfunction "1_P$1") (pintype "passive"))
      (node (ref "C34") (pin "P$1") (pinfunction "1_P$1") (pintype "passive"))
      (node (ref "C6") (pin "P$1") (pinfunction "1_P$1") (pintype "passive"))
      (node (ref "JLINK") (pin "5") (pinfunction "5_5") (pintype "passive"))
      (node (ref "L12") (pin "P$2") (pinfunction "2_P$2") (pintype "passive"))
      (node (ref "Q2") (pin "2") (pinfunction "S_2") (pintype "passive"))
      (node (ref "R1") (pin "P$2") (pinfunction "P$2_P$2") (pintype "passive"))
      (node (ref "R21") (pin "P$2") (pinfunction "P$2_P$2") (pintype "passive"))
      (node (ref "R22") (pin "P$2") (pinfunction "P$2_P$2") (pintype "passive"))
      (node (ref "U11") (pin "6") (pinfunction "VDD_1_6") (pintype "power_in"))
      (node (ref "U11") (pin "8") (pinfunction "VDD_2_8") (pintype "power_in"))
      (node (ref "U12") (pin "6") (pinfunction "VDD_1_6") (pintype "power_in"))
      (node (ref "U12") (pin "8") (pinfunction "VDD_2_8") (pintype "power_in"))
      (node (ref "U13") (pin "1") (pinfunction "VDD_1") (pintype "bidirectional"))
      (node (ref "U13") (pin "17") (pinfunction "VDD_17") (pintype "bidirectional"))
      (node (ref "U13") (pin "5") (pinfunction "VDDA_5") (pintype "bidirectional"))
      (node (ref "U2") (pin "P$6") (pinfunction "VBAT_P$6") (pintype "bidirectional"))
      (node (ref "U8") (pin "4") (pinfunction "VDD_4") (pintype "bidirectional"))
    )
    (net (code "2") (name "BOOT0") (class "Default")
      (node (ref "BOOT0") (pin "TP") (pinfunction "TP_TP") (pintype "input"))
      (node (ref "R23") (pin "P$1") (pinfunction "P$1_P$1") (pintype "passive"))
      (node (ref "U13") (pin "31") (pinfunction "BOOT0_31") (pintype "bidirectional"))
    )
    (net (code "3") (name "CS1") (class "Default")
      (node (ref "U11") (pin "15") (pinfunction "NSEL_15") (pintype "input"))
      (node (ref "U13") (pin "10") (pinfunction "PA4_10") (pintype "bidirectional"))
    )
    (net (code "4") (name "CS2") (class "Default")
      (node (ref "U12") (pin "15") (pinfunction "NSEL_15") (pintype "input"))
      (node (ref "U13") (pin "6") (pinfunction "PA0_6") (pintype "bidirectional"))
    )
    (net (code "5") (name "GND") (class "Default")
      (node (ref "C1") (pin "P$2") (pinfunction "2_P$2") (pintype "passive"))
      (node (ref "C11") (pin "P$2") (pinfunction "2_P$2") (pintype "passive"))
      (node (ref "C13") (pin "P$2") (pinfunction "2_P$2") (pintype "passive"))
      (node (ref "C14") (pin "P$2") (pinfunction "2_P$2") (pintype "passive"))
      (node (ref "C15") (pin "P$2") (pinfunction "2_P$2") (pintype "passive"))
      (node (ref "C16") (pin "P$2") (pinfunction "2_P$2") (pintype "passive"))
      (node (ref "C17") (pin "P$2") (pinfunction "2_P$2") (pintype "passive"))
      (node (ref "C21") (pin "P$2") (pinfunction "2_P$2") (pintype "passive"))
      (node (ref "C23") (pin "P$2") (pinfunction "2_P$2") (pintype "passive"))
      (node (ref "C26") (pin "P$2") (pinfunction "2_P$2") (pintype "passive"))
      (node (ref "C28") (pin "P$2") (pinfunction "2_P$2") (pintype "passive"))
      (node (ref "C3") (pin "P$2") (pinfunction "2_P$2") (pintype "passive"))
      (node (ref "C30") (pin "P$2") (pinfunction "2_P$2") (pintype "passive"))
      (node (ref "C32") (pin "P$2") (pinfunction "2_P$2") (pintype "passive"))
      (node (ref "C34") (pin "P$2") (pinfunction "2_P$2") (pintype "passive"))
      (node (ref "C36") (pin "P$2") (pinfunction "2_P$2") (pintype "passive"))
      (node (ref "C37") (pin "P$2") (pinfunction "2_P$2") (pintype "passive"))
      (node (ref "C39") (pin "P$2") (pinfunction "2_P$2") (pintype "passive"))
      (node (ref "C4") (pin "P$2") (pinfunction "2_P$2") (pintype "passive"))
      (node (ref "C42") (pin "P$2") (pinfunction "2_P$2") (pintype "passive"))
      (node (ref "C43") (pin "P$2") (pinfunction "2_P$2") (pintype "passive"))
      (node (ref "C47") (pin "P$2") (pinfunction "2_P$2") (pintype "passive"))
      (node (ref "C49") (pin "P$2") (pinfunction "2_P$2") (pintype "passive"))
      (node (ref "C5") (pin "P$2") (pinfunction "2_P$2") (pintype "passive"))
      (node (ref "C52") (pin "P$2") (pinfunction "2_P$2") (pintype "passive"))
      (node (ref "C53") (pin "P$2") (pinfunction "2_P$2") (pintype "passive"))
      (node (ref "C6") (pin "P$2") (pinfunction "2_P$2") (pintype "passive"))
      (node (ref "C7") (pin "P$2") (pinfunction "2_P$2") (pintype "passive"))
      (node (ref "C8") (pin "P$2") (pinfunction "2_P$2") (pintype "passive"))
      (node (ref "D3") (pin "C") (pinfunction "P$2_C") (pintype "bidirectional"))
      (node (ref "D4") (pin "A") (pinfunction "A_A") (pintype "passive"))
      (node (ref "GND1") (pin "TP") (pinfunction "TP_TP") (pintype "input"))
      (node (ref "GND2") (pin "TP") (pinfunction "TP_TP") (pintype "input"))
      (node (ref "J$1") (pin "GND@0") (pinfunction "GND_GND@0") (pintype "bidirectional"))
      (node (ref "J$1") (pin "GND@1") (pinfunction "GND_GND@1") (pintype "bidirectional"))
      (node (ref "J$1") (pin "GND@2") (pinfunction "GND_GND@2") (pintype "bidirectional"))
      (node (ref "J$1") (pin "GND@3") (pinfunction "GND_GND@3") (pintype "bidirectional"))
      (node (ref "JLINK") (pin "1") (pinfunction "1_1") (pintype "passive"))
      (node (ref "JP1") (pin "8") (pinfunction "8_8") (pintype "bidirectional"))
      (node (ref "L14") (pin "P$1") (pinfunction "1_P$1") (pintype "passive"))
      (node (ref "Q1") (pin "1") (pinfunction "G_1") (pintype "passive"))
      (node (ref "R12") (pin "P$1") (pinfunction "P$1_P$1") (pintype "passive"))
      (node (ref "R18") (pin "P$1") (pinfunction "P$1_P$1") (pintype "passive"))
      (node (ref "R23") (pin "P$2") (pinfunction "P$2_P$2") (pintype "passive"))
      (node (ref "R24") (pin "P$1") (pinfunction "P$1_P$1") (pintype "passive"))
      (node (ref "R4") (pin "P$1") (pinfunction "P$1_P$1") (pintype "passive"))
      (node (ref "S1") (pin "P$2") (pinfunction "S2_P$2") (pintype "bidirectional"))
      (node (ref "SWDIO1") (pin "TP") (pinfunction "TP_TP") (pintype "input"))
      (node (ref "SWDIO2") (pin "TP") (pinfunction "TP_TP") (pintype "input"))
      (node (ref "SWDIO3") (pin "TP") (pinfunction "TP_TP") (pintype "input"))
      (node (ref "SWDIO4") (pin "TP") (pinfunction "TP_TP") (pintype "input"))
      (node (ref "SWDIO5") (pin "TP") (pinfunction "TP_TP") (pintype "input"))
      (node (ref "SWDIO6") (pin "TP") (pinfunction "TP_TP") (pintype "input"))
      (node (ref "U1") (pin "2") (pinfunction "GND_2") (pintype "bidirectional"))
      (node (ref "U11") (pin "18") (pinfunction "GNDX_18") (pintype "bidirectional"))
      (node (ref "U11") (pin "3") (pinfunction "RXN_3") (pintype "input"))
      (node (ref "U11") (pin "5") (pinfunction "NC_5") (pintype "bidirectional"))
      (node (ref "U11") (pin "EXP") (pinfunction "PAD_EXP") (pintype "bidirectional"))
      (node (ref "U12") (pin "18") (pinfunction "GNDX_18") (pintype "bidirectional"))
      (node (ref "U12") (pin "3") (pinfunction "RXN_3") (pintype "input"))
      (node (ref "U12") (pin "5") (pinfunction "NC_5") (pintype "bidirectional"))
      (node (ref "U12") (pin "EXP") (pinfunction "PAD_EXP") (pintype "bidirectional"))
      (node (ref "U13") (pin "16") (pinfunction "VSS_16") (pintype "bidirectional"))
      (node (ref "U13") (pin "32") (pinfunction "VSS_32") (pintype "bidirectional"))
      (node (ref "U13") (pin "EXP") (pinfunction "PAD_EXP") (pintype "bidirectional"))
      (node (ref "U14") (pin "1") (pinfunction "S_1") (pintype "bidirectional"))
      (node (ref "U14") (pin "4") (pinfunction "S_4") (pintype "bidirectional"))
      (node (ref "U17") (pin "1") (pinfunction "S_1") (pintype "bidirectional"))
      (node (ref "U17") (pin "4") (pinfunction "S_4") (pintype "bidirectional"))
      (node (ref "U2") (pin "P$1") (pinfunction "GND_P$1") (pintype "bidirectional"))
      (node (ref "U2") (pin "P$10") (pinfunction "GND_P$10") (pintype "bidirectional"))
      (node (ref "U2") (pin "P$12") (pinfunction "GND_P$12") (pintype "bidirectional"))
      (node (ref "U3") (pin "P$4") (pinfunction "GND_P$4") (pintype "bidirectional"))
      (node (ref "U3") (pin "P$7") (pinfunction "GND_P$7") (pintype "bidirectional"))
      (node (ref "U5") (pin "2") (pinfunction "GND_2") (pintype "bidirectional"))
      (node (ref "U5") (pin "4") (pinfunction "GND_4") (pintype "bidirectional"))
      (node (ref "U5") (pin "5") (pinfunction "GND_5") (pintype "bidirectional"))
      (node (ref "U6") (pin "3") (pinfunction "P$3_3") (pintype "bidirectional"))
      (node (ref "U7") (pin "2") (pinfunction "S_2") (pintype "passive"))
      (node (ref "U7") (pin "2@1") (pinfunction "PAD_2@1") (pintype "bidirectional"))
      (node (ref "U8") (pin "2") (pinfunction "GND_2") (pintype "bidirectional"))
      (node (ref "U9") (pin "P$3") (pinfunction "GND_P$3") (pintype "bidirectional"))
      (node (ref "X1") (pin "2") (pinfunction "G2_2") (pintype "power_in"))
      (node (ref "X1") (pin "4") (pinfunction "G1_4") (pintype "power_in"))
      (node (ref "X2") (pin "2") (pinfunction "G2_2") (pintype "power_in"))
      (node (ref "X2") (pin "4") (pinfunction "G1_4") (pintype "power_in"))
    )
    (net (code "6") (name "GPS_1PPS") (class "Default")
      (node (ref "U13") (pin "8") (pinfunction "PA2_8") (pintype "bidirectional"))
      (node (ref "U2") (pin "P$4") (pinfunction "1PPS_P$4") (pintype "bidirectional"))
    )
    (net (code "7") (name "GPS_EN") (class "Default")
      (node (ref "Q2") (pin "1") (pinfunction "G_1") (pintype "passive"))
      (node (ref "R1") (pin "P$1") (pinfunction "P$1_P$1") (pintype "passive"))
      (node (ref "U13") (pin "2") (pinfunction "OSC_IN/PC14_2") (pintype "bidirectional"))
    )
    (net (code "8") (name "GPS_STATUS") (class "Default")
      (node (ref "U13") (pin "21") (pinfunction "PA11_21") (pintype "bidirectional"))
      (node (ref "U14") (pin "5") (pinfunction "G_5") (pintype "bidirectional"))
    )
    (net (code "9") (name "GPS_UART_TX") (class "Default")
      (node (ref "U13") (pin "9") (pinfunction "PA3_9") (pintype "bidirectional"))
      (node (ref "U2") (pin "P$2") (pinfunction "TX_P$2") (pintype "bidirectional"))
    )
    (net (code "10") (name "HOST_GPS_STATUS") (class "Default")
      (node (ref "JP1") (pin "4") (pinfunction "4_4") (pintype "bidirectional"))
      (node (ref "R14") (pin "P$2") (pinfunction "P$2_P$2") (pintype "passive"))
      (node (ref "U9") (pin "P$2") (pinfunction "C2_P$2") (pintype "bidirectional"))
    )
    (net (code "11") (name "HOST_RX_STATUS") (class "Default")
      (node (ref "JP1") (pin "6") (pinfunction "6_6") (pintype "bidirectional"))
      (node (ref "R15") (pin "P$2") (pinfunction "P$2_P$2") (pintype "passive"))
      (node (ref "U9") (pin "P$7") (pinfunction "C6_P$7") (pintype "bidirectional"))
    )
    (net (code "12") (name "HOST_TX_OFF") (class "Default")
      (node (ref "JP1") (pin "2") (pinfunction "2_2") (pintype "bidirectional"))
      (node (ref "R18") (pin "P$2") (pinfunction "P$2_P$2") (pintype "passive"))
      (node (ref "U17") (pin "2") (pinfunction "G_2") (pintype "bidirectional"))
      (node (ref "U9") (pin "P$1") (pinfunction "C1_P$1") (pintype "bidirectional"))
    )
    (net (code "13") (name "HOST_TX_STATUS") (class "Default")
      (node (ref "JP1") (pin "7") (pinfunction "7_7") (pintype "bidirectional"))
      (node (ref "R17") (pin "P$2") (pinfunction "P$2_P$2") (pintype "passive"))
      (node (ref "U9") (pin "P$6") (pinfunction "C5_P$6") (pintype "bidirectional"))
    )
    (net (code "14") (name "HOST_UART_RX") (class "Default")
      (node (ref "JP1") (pin "5") (pinfunction "5_5") (pintype "bidirectional"))
      (node (ref "R13") (pin "P$2") (pinfunction "P$2_P$2") (pintype "passive"))
      (node (ref "U9") (pin "P$8") (pinfunction "C7_P$8") (pintype "bidirectional"))
    )
    (net (code "15") (name "HOST_UART_TX") (class "Default")
      (node (ref "JP1") (pin "3") (pinfunction "3_3") (pintype "bidirectional"))
      (node (ref "R2") (pin "P$2") (pinfunction "P$2_P$2") (pintype "passive"))
      (node (ref "U9") (pin "P$9") (pinfunction "C8_P$9") (pintype "bidirectional"))
    )
    (net (code "16") (name "LNA_PWR") (class "Default")
      (node (ref "R10") (pin "P$1") (pinfunction "P$1_P$1") (pintype "passive"))
      (node (ref "U13") (pin "29") (pinfunction "PB6_29") (pintype "bidirectional"))
      (node (ref "V_LNA") (pin "TP") (pinfunction "TP_TP") (pintype "input"))
    )
    (net (code "17") (name "MCU_TX_OFF") (class "Default")
      (node (ref "U13") (pin "22") (pinfunction "PA12_22") (pintype "bidirectional"))
      (node (ref "U17") (pin "6") (pinfunction "D_6") (pintype "bidirectional"))
    )
    (net (code "18") (name "MCU_UART_RX") (class "Default")
      (node (ref "R2") (pin "P$1") (pinfunction "P$1_P$1") (pintype "passive"))
      (node (ref "RX") (pin "TP") (pinfunction "TP_TP") (pintype "input"))
      (node (ref "U13") (pin "20") (pinfunction "PA10_20") (pintype "bidirectional"))
      (node (ref "U6") (pin "1") (pinfunction "P$1_1") (pintype "bidirectional"))
    )
    (net (code "19") (name "MCU_UART_TX") (class "Default")
      (node (ref "R13") (pin "P$1") (pinfunction "P$1_P$1") (pintype "passive"))
      (node (ref "TX") (pin "TP") (pinfunction "TP_TP") (pintype "input"))
      (node (ref "U13") (pin "19") (pinfunction "PA9_19") (pintype "bidirectional"))
      (node (ref "U6") (pin "2") (pinfunction "P$2_2") (pintype "bidirectional"))
    )
    (net (code "20") (name "MISO") (class "Default")
      (node (ref "U11") (pin "13") (pinfunction "SDO_13") (pintype "output"))
      (node (ref "U12") (pin "13") (pinfunction "SDO_13") (pintype "output"))
      (node (ref "U13") (pin "12") (pinfunction "PA6_12") (pintype "bidirectional"))
    )
    (net (code "21") (name "MOSI") (class "Default")
      (node (ref "U11") (pin "14") (pinfunction "SDI_14") (pintype "input"))
      (node (ref "U12") (pin "14") (pinfunction "SDI_14") (pintype "input"))
      (node (ref "U13") (pin "13") (pinfunction "PA7_13") (pintype "bidirectional"))
    )
    (net (code "22") (name "NRST") (class "Default")
      (node (ref "JLINK") (pin "2") (pinfunction "2_2") (pintype "passive"))
      (node (ref "NRST") (pin "TP") (pinfunction "TP_TP") (pintype "input"))
      (node (ref "S1") (pin "P$1") (pinfunction "S1_P$1") (pintype "bidirectional"))
      (node (ref "U13") (pin "4") (pinfunction "NRST_4") (pintype "bidirectional"))
    )
    (net (code "23") (name "Net-(C1-1)") (class "Default")
      (node (ref "C1") (pin "P$1") (pinfunction "1_P$1") (pintype "passive"))
      (node (ref "C43") (pin "P$1") (pinfunction "1_P$1") (pintype "passive"))
      (node (ref "L2") (pin "P$2") (pinfunction "2_P$2") (pintype "passive"))
      (node (ref "U1") (pin "4") (pinfunction "EN_4") (pintype "bidirectional"))
      (node (ref "U1") (pin "5") (pinfunction "IN_5") (pintype "bidirectional"))
    )
    (net (code "24") (name "Net-(C2-1)") (class "Default")
      (node (ref "C2") (pin "P$1") (pinfunction "1_P$1") (pintype "passive"))
      (node (ref "U1") (pin "1") (pinfunction "BS_1") (pintype "bidirectional"))
    )
    (net (code "25") (name "Net-(C2-2)") (class "Default")
      (node (ref "C2") (pin "P$2") (pinfunction "2_P$2") (pintype "passive"))
      (node (ref "D4") (pin "C") (pinfunction "C_C") (pintype "passive"))
      (node (ref "L12") (pin "P$1") (pinfunction "1_P$1") (pintype "passive"))
      (node (ref "U1") (pin "6") (pinfunction "SW_6") (pintype "bidirectional"))
    )
    (net (code "26") (name "Net-(C3-1)") (class "Default")
      (node (ref "C3") (pin "P$1") (pinfunction "1_P$1") (pintype "passive"))
      (node (ref "C5") (pin "P$1") (pinfunction "1_P$1") (pintype "passive"))
      (node (ref "Q2") (pin "3") (pinfunction "D_3") (pintype "passive"))
      (node (ref "U2") (pin "P$8") (pinfunction "VCC_P$8") (pintype "bidirectional"))
    )
    (net (code "27") (name "Net-(C9-1)") (class "Default")
      (node (ref "C9") (pin "P$1") (pinfunction "1_P$1") (pintype "passive"))
      (node (ref "L8") (pin "P$2") (pinfunction "2_P$2") (pintype "passive"))
    )
    (net (code "28") (name "Net-(C10-1)") (class "Default")
      (node (ref "C10") (pin "P$1") (pinfunction "1_P$1") (pintype "passive"))
      (node (ref "C8") (pin "P$1") (pinfunction "1_P$1") (pintype "passive"))
      (node (ref "C9") (pin "P$2") (pinfunction "2_P$2") (pintype "passive"))
      (node (ref "L14") (pin "P$2") (pinfunction "2_P$2") (pintype "passive"))
    )
    (net (code "29") (name "Net-(C10-2)") (class "Default")
      (node (ref "C10") (pin "P$2") (pinfunction "2_P$2") (pintype "passive"))
      (node (ref "L13") (pin "P$1") (pinfunction "1_P$1") (pintype "passive"))
    )
    (net (code "30") (name "Net-(C12-1)") (class "Default")
      (node (ref "C12") (pin "P$1") (pinfunction "1_P$1") (pintype "passive"))
      (node (ref "L13") (pin "P$2") (pinfunction "2_P$2") (pintype "passive"))
    )
    (net (code "31") (name "Net-(C12-2)") (class "Default")
      (node (ref "C12") (pin "P$2") (pinfunction "2_P$2") (pintype "passive"))
      (node (ref "U5") (pin "6") (pinfunction "IN_6") (pintype "bidirectional"))
    )
    (net (code "32") (name "Net-(C13-1)") (class "Default")
      (node (ref "C13") (pin "P$1") (pinfunction "1_P$1") (pintype "passive"))
      (node (ref "R10") (pin "P$2") (pinfunction "P$2_P$2") (pintype "passive"))
      (node (ref "U5") (pin "1") (pinfunction "VCC_1") (pintype "bidirectional"))
    )
    (net (code "33") (name "Net-(C18-1)") (class "Default")
      (node (ref "C18") (pin "P$1") (pinfunction "1_P$1") (pintype "passive"))
      (node (ref "U5") (pin "3") (pinfunction "OUT_3") (pintype "bidirectional"))
    )
    (net (code "34") (name "Net-(C21-1)") (class "Default")
      (node (ref "C21") (pin "P$1") (pinfunction "1_P$1") (pintype "passive"))
      (node (ref "L5") (pin "P$1") (pinfunction "1_P$1") (pintype "passive"))
      (node (ref "R22") (pin "P$1") (pinfunction "P$1_P$1") (pintype "passive"))
    )
    (net (code "35") (name "Net-(C22-1)") (class "Default")
      (node (ref "C22") (pin "P$1") (pinfunction "1_P$1") (pintype "passive"))
      (node (ref "L5") (pin "P$2") (pinfunction "2_P$2") (pintype "passive"))
      (node (ref "U11") (pin "4") (pinfunction "TX_4") (pintype "output"))
    )
    (net (code "36") (name "Net-(C22-2)") (class "Default")
      (node (ref "C22") (pin "P$2") (pinfunction "2_P$2") (pintype "passive"))
      (node (ref "L1") (pin "P$1") (pinfunction "1_P$1") (pintype "passive"))
    )
    (net (code "37") (name "Net-(C23-1)") (class "Default")
      (node (ref "C23") (pin "P$1") (pinfunction "1_P$1") (pintype "passive"))
      (node (ref "L1") (pin "P$2") (pinfunction "2_P$2") (pintype "passive"))
      (node (ref "L6") (pin "P$1") (pinfunction "1_P$1") (pintype "passive"))
    )
    (net (code "38") (name "Net-(C29-2)") (class "Default")
      (node (ref "C29") (pin "P$2") (pinfunction "2_P$2") (pintype "passive"))
      (node (ref "C30") (pin "P$1") (pinfunction "1_P$1") (pintype "passive"))
      (node (ref "L3") (pin "P$1") (pinfunction "1_P$1") (pintype "passive"))
    )
    (net (code "39") (name "Net-(C36-1)") (class "Default")
      (node (ref "C36") (pin "P$1") (pinfunction "1_P$1") (pintype "passive"))
      (node (ref "L10") (pin "P$1") (pinfunction "1_P$1") (pintype "passive"))
      (node (ref "L9") (pin "P$2") (pinfunction "2_P$2") (pintype "passive"))
    )
    (net (code "40") (name "Net-(C37-1)") (class "Default")
      (node (ref "C37") (pin "P$1") (pinfunction "1_P$1") (pintype "passive"))
      (node (ref "C39") (pin "P$1") (pinfunction "1_P$1") (pintype "passive"))
      (node (ref "L4") (pin "P$2") (pinfunction "2_P$2") (pintype "passive"))
      (node (ref "L9") (pin "P$1") (pinfunction "1_P$1") (pintype "passive"))
      (node (ref "U7") (pin "3") (pinfunction "D_3") (pintype "passive"))
    )
    (net (code "41") (name "Net-(C42-1)") (class "Default")
      (node (ref "C42") (pin "P$1") (pinfunction "1_P$1") (pintype "passive"))
      (node (ref "C52") (pin "P$1") (pinfunction "1_P$1") (pintype "passive"))
      (node (ref "L10") (pin "P$2") (pinfunction "2_P$2") (pintype "passive"))
      (node (ref "L23") (pin "P$1") (pinfunction "1_P$1") (pintype "passive"))
    )
    (net (code "42") (name "Net-(C44-1)") (class "Default")
      (node (ref "C44") (pin "P$1") (pinfunction "1_P$1") (pintype "passive"))
      (node (ref "C53") (pin "P$1") (pinfunction "1_P$1") (pintype "passive"))
      (node (ref "L23") (pin "P$2") (pinfunction "2_P$2") (pintype "passive"))
    )
    (net (code "43") (name "Net-(J$1-SIGNAL)") (class "Default")
      (node (ref "J$1") (pin "SIG") (pinfunction "SIGNAL_SIG") (pintype "bidirectional"))
      (node (ref "RF") (pin "TP") (pinfunction "TP_TP") (pintype "input"))
      (node (ref "U8") (pin "5") (pinfunction "RFIN_5") (pintype "bidirectional"))
    )
    (net (code "44") (name "Net-(L17-1)") (class "Default")
      (node (ref "L17") (pin "P$1") (pinfunction "1_P$1") (pintype "passive"))
      (node (ref "L3") (pin "P$2") (pinfunction "2_P$2") (pintype "passive"))
      (node (ref "U7") (pin "1") (pinfunction "G_1") (pintype "passive"))
    )
    (net (code "45") (name "Net-(U1-FB)") (class "Default")
      (node (ref "R21") (pin "P$1") (pinfunction "P$1_P$1") (pintype "passive"))
      (node (ref "R24") (pin "P$2") (pinfunction "P$2_P$2") (pintype "passive"))
      (node (ref "U1") (pin "3") (pinfunction "FB_3") (pintype "bidirectional"))
    )
    (net (code "46") (name "Net-(U2-RFIN)") (class "Default")
      (node (ref "U2") (pin "P$11") (pinfunction "RFIN_P$11") (pintype "bidirectional"))
      (node (ref "Z1") (pin "P$2") (pinfunction "P$2_P$2") (pintype "passive"))
    )
    (net (code "47") (name "Net-(U3-ADJ)") (class "Default")
      (node (ref "R4") (pin "P$2") (pinfunction "P$2_P$2") (pintype "passive"))
      (node (ref "R5") (pin "P$1") (pinfunction "P$1_P$1") (pintype "passive"))
      (node (ref "U3") (pin "P$2") (pinfunction "ADJ_P$2") (pintype "bidirectional"))
    )
    (net (code "48") (name "Net-(U10-RF)") (class "Default")
      (node (ref "U10") (pin "P$1") (pinfunction "RF_P$1") (pintype "bidirectional"))
      (node (ref "Z1") (pin "P$1") (pinfunction "P$1_P$1") (pintype "passive"))
    )
    (net (code "49") (name "Net-(U11-XIN)") (class "Default")
      (node (ref "U11") (pin "17") (pinfunction "XIN_17") (pintype "input"))
      (node (ref "X1") (pin "3") (pinfunction "X2_3") (pintype "bidirectional"))
    )
    (net (code "50") (name "Net-(U11-XOUT)") (class "Default")
      (node (ref "U11") (pin "16") (pinfunction "XOUT_16") (pintype "bidirectional"))
      (node (ref "X1") (pin "1") (pinfunction "X1_1") (pintype "bidirectional"))
    )
    (net (code "51") (name "Net-(U12-XIN)") (class "Default")
      (node (ref "U12") (pin "17") (pinfunction "XIN_17") (pintype "input"))
      (node (ref "X2") (pin "3") (pinfunction "X2_3") (pintype "bidirectional"))
    )
    (net (code "52") (name "Net-(U12-XOUT)") (class "Default")
      (node (ref "U12") (pin "16") (pinfunction "XOUT_16") (pintype "bidirectional"))
      (node (ref "X2") (pin "1") (pinfunction "X1_1") (pintype "bidirectional"))
    )
    (net (code "53") (name "Net-(U14A-D)") (class "Default")
      (node (ref "R14") (pin "P$1") (pinfunction "P$1_P$1") (pintype "passive"))
      (node (ref "U14") (pin "3") (pinfunction "D_3") (pintype "bidirectional"))
    )
    (net (code "54") (name "Net-(U14B-D)") (class "Default")
      (node (ref "R15") (pin "P$1") (pinfunction "P$1_P$1") (pintype "passive"))
      (node (ref "U14") (pin "6") (pinfunction "D_6") (pintype "bidirectional"))
    )
    (net (code "55") (name "Net-(U17A-D)") (class "Default")
      (node (ref "R17") (pin "P$1") (pinfunction "P$1_P$1") (pintype "passive"))
      (node (ref "U17") (pin "3") (pinfunction "D_3") (pintype "bidirectional"))
    )
    (net (code "56") (name "PA_GATE_BIAS") (class "Default")
      (node (ref "C11") (pin "P$1") (pinfunction "1_P$1") (pintype "passive"))
      (node (ref "L17") (pin "P$2") (pinfunction "2_P$2") (pintype "passive"))
      (node (ref "R11") (pin "P$1") (pinfunction "P$1_P$1") (pintype "passive"))
      (node (ref "R12") (pin "P$2") (pinfunction "P$2_P$2") (pintype "passive"))
    )
    (net (code "57") (name "PA_IN") (class "Default")
      (node (ref "C29") (pin "P$1") (pinfunction "1_P$1") (pintype "passive"))
      (node (ref "L6") (pin "P$2") (pinfunction "2_P$2") (pintype "passive"))
    )
    (net (code "58") (name "PA_OUT") (class "Default")
      (node (ref "C44") (pin "P$2") (pinfunction "2_P$2") (pintype "passive"))
      (node (ref "U8") (pin "1") (pinfunction "RF2_1") (pintype "bidirectional"))
    )
    (net (code "59") (name "RFSW_CTRL") (class "Default")
      (node (ref "U13") (pin "30") (pinfunction "PB7_30") (pintype "bidirectional"))
      (node (ref "U8") (pin "6") (pinfunction "CTRL_6") (pintype "bidirectional"))
    )
    (net (code "60") (name "RF_IN") (class "Default")
      (node (ref "L8") (pin "P$1") (pinfunction "1_P$1") (pintype "passive"))
      (node (ref "U8") (pin "3") (pinfunction "RF1_3") (pintype "bidirectional"))
    )
    (net (code "61") (name "RX_IC_CLK") (class "Default")
      (node (ref "U12") (pin "20") (pinfunction "GPIO3_20") (pintype "bidirectional"))
      (node (ref "U13") (pin "26") (pinfunction "PB3_26") (pintype "bidirectional"))
    )
    (net (code "62") (name "RX_IC_DATA") (class "Default")
      (node (ref "U12") (pin "10") (pinfunction "GPIO1_10") (pintype "bidirectional"))
      (node (ref "U13") (pin "27") (pinfunction "PB4_27") (pintype "bidirectional"))
    )
    (net (code "63") (name "RX_IN") (class "Default")
      (node (ref "C18") (pin "P$2") (pinfunction "2_P$2") (pintype "passive"))
      (node (ref "U11") (pin "2") (pinfunction "RXP_2") (pintype "input"))
      (node (ref "U12") (pin "2") (pinfunction "RXP_2") (pintype "input"))
    )
    (net (code "64") (name "RX_STATUS") (class "Default")
      (node (ref "U13") (pin "7") (pinfunction "PA1_7") (pintype "bidirectional"))
      (node (ref "U14") (pin "2") (pinfunction "G_2") (pintype "bidirectional"))
    )
    (net (code "65") (name "SCK") (class "Default")
      (node (ref "U11") (pin "12") (pinfunction "SCLK_12") (pintype "input"))
      (node (ref "U12") (pin "12") (pinfunction "SCLK_12") (pintype "input"))
      (node (ref "U13") (pin "11") (pinfunction "PA5_11") (pintype "bidirectional"))
    )
    (net (code "66") (name "SDN1") (class "Default")
      (node (ref "U11") (pin "1") (pinfunction "SDN_1") (pintype "input"))
      (node (ref "U13") (pin "14") (pinfunction "PB0_14") (pintype "bidirectional"))
    )
    (net (code "67") (name "SDN2") (class "Default")
      (node (ref "U12") (pin "1") (pinfunction "SDN_1") (pintype "input"))
      (node (ref "U13") (pin "25") (pinfunction "PA15_25") (pintype "bidirectional"))
    )
    (net (code "68") (name "SWCLK") (class "Default")
      (node (ref "JLINK") (pin "3") (pinfunction "3_3") (pintype "passive"))
      (node (ref "SWCLK") (pin "TP") (pinfunction "TP_TP") (pintype "input"))
      (node (ref "U13") (pin "24") (pinfunction "PA14_24") (pintype "bidirectional"))
    )
    (net (code "69") (name "SWDIO") (class "Default")
      (node (ref "JLINK") (pin "4") (pinfunction "4_4") (pintype "passive"))
      (node (ref "SWDIO") (pin "TP") (pinfunction "TP_TP") (pintype "input"))
      (node (ref "U13") (pin "23") (pinfunction "PA13_23") (pintype "bidirectional"))
    )
    (net (code "70") (name "TRX_IC_CLOCK") (class "Default")
      (node (ref "U11") (pin "19") (pinfunction "GPIO2_19") (pintype "bidirectional"))
      (node (ref "U13") (pin "3") (pinfunction "OSC_OUT/PC15_3") (pintype "bidirectional"))
    )
    (net (code "71") (name "TRX_IC_DATA") (class "Default")
      (node (ref "U11") (pin "10") (pinfunction "GPIO1_10") (pintype "bidirectional"))
      (node (ref "U13") (pin "15") (pinfunction "PB1_15") (pintype "bidirectional"))
    )
    (net (code "72") (name "TX_STATUS") (class "Default")
      (node (ref "U13") (pin "28") (pinfunction "PB5_28") (pintype "bidirectional"))
      (node (ref "U17") (pin "5") (pinfunction "G_5") (pintype "bidirectional"))
    )
    (net (code "73") (name "V_IN") (class "Default")
      (node (ref "D3") (pin "A") (pinfunction "P$1_A") (pintype "bidirectional"))
      (node (ref "JP1") (pin "1") (pinfunction "1_1") (pintype "bidirectional"))
      (node (ref "Q1") (pin "3") (pinfunction "D_3") (pintype "passive"))
      (node (ref "V_IN") (pin "TP") (pinfunction "TP_TP") (pintype "input"))
    )
    (net (code "74") (name "V_PA") (class "Default")
      (node (ref "C49") (pin "P$1") (pinfunction "1_P$1") (pintype "passive"))
      (node (ref "C7") (pin "P$1") (pinfunction "1_P$1") (pintype "passive"))
      (node (ref "L4") (pin "P$1") (pinfunction "1_P$1") (pintype "passive"))
      (node (ref "R5") (pin "P$2") (pinfunction "P$2_P$2") (pintype "passive"))
      (node (ref "U3") (pin "P$1") (pinfunction "VOUT_P$1") (pintype "bidirectional"))
      (node (ref "V_PA") (pin "TP") (pinfunction "TP_TP") (pintype "input"))
    )
    (net (code "75") (name "V_PA_BIAS") (class "Default")
      (node (ref "R11") (pin "P$2") (pinfunction "P$2_P$2") (pintype "passive"))
      (node (ref "U13") (pin "18") (pinfunction "PA8_18") (pintype "bidirectional"))
    )
    (net (code "76") (name "V_PROT") (class "Default")
      (node (ref "C4") (pin "P$1") (pinfunction "1_P$1") (pintype "passive"))
      (node (ref "C47") (pin "P$1") (pinfunction "1_P$1") (pintype "passive"))
      (node (ref "L2") (pin "P$1") (pinfunction "1_P$1") (pintype "passive"))
      (node (ref "Q1") (pin "2") (pinfunction "S_2") (pintype "passive"))
      (node (ref "U3") (pin "P$5") (pinfunction "EN_P$5") (pintype "bidirectional"))
      (node (ref "U3") (pin "P$6") (pinfunction "VIN_P$6") (pintype "bidirectional"))
    )
    (net (code "77") (name "unconnected-(S1-S1-PadP$4)") (class "Default")
      (node (ref "S1") (pin "P$4") (pinfunction "S1_P$4") (pintype "bidirectional"))
    )
    (net (code "78") (name "unconnected-(S1-S2-PadP$3)") (class "Default")
      (node (ref "S1") (pin "P$3") (pinfunction "S2_P$3") (pintype "bidirectional"))
    )
    (net (code "79") (name "unconnected-(U2-RX-PadP$3)") (class "Default")
      (node (ref "U2") (pin "P$3") (pinfunction "RX_P$3") (pintype "bidirectional"))
    )
    (net (code "80") (name "unconnected-(U3-PG-PadP$3)") (class "Default")
      (node (ref "U3") (pin "P$3") (pinfunction "PG_P$3") (pintype "bidirectional"))
    )
    (net (code "81") (name "unconnected-(U9-C3-PadP$4)") (class "Default")
      (node (ref "U9") (pin "P$4") (pinfunction "C3_P$4") (pintype "bidirectional"))
    )
    (net (code "82") (name "unconnected-(U9-C4-PadP$5)") (class "Default")
      (node (ref "U9") (pin "P$5") (pinfunction "C4_P$5") (pintype "bidirectional"))
    )
    (net (code "83") (name "unconnected-(U10-PAD-PadP$2)") (class "Default")
      (node (ref "U10") (pin "P$2") (pinfunction "PAD_P$2") (pintype "bidirectional"))
    )
    (net (code "84") (name "unconnected-(U11-GPIO0-Pad9)") (class "Default")
      (node (ref "U11") (pin "9") (pinfunction "GPIO0_9") (pintype "bidirectional"))
    )
    (net (code "85") (name "unconnected-(U11-GPIO3-Pad20)") (class "Default")
      (node (ref "U11") (pin "20") (pinfunction "GPIO3_20") (pintype "bidirectional"))
    )
    (net (code "86") (name "unconnected-(U11-NIRQ-Pad11)") (class "Default")
      (node (ref "U11") (pin "11") (pinfunction "NIRQ_11") (pintype "bidirectional"))
    )
    (net (code "87") (name "unconnected-(U11-TXRAMP-Pad7)") (class "Default")
      (node (ref "U11") (pin "7") (pinfunction "TXRAMP_7") (pintype "bidirectional"))
    )
    (net (code "88") (name "unconnected-(U12-GPIO0-Pad9)") (class "Default")
      (node (ref "U12") (pin "9") (pinfunction "GPIO0_9") (pintype "bidirectional"))
    )
    (net (code "89") (name "unconnected-(U12-GPIO2-Pad19)") (class "Default")
      (node (ref "U12") (pin "19") (pinfunction "GPIO2_19") (pintype "bidirectional"))
    )
    (net (code "90") (name "unconnected-(U12-NIRQ-Pad11)") (class "Default")
      (node (ref "U12") (pin "11") (pinfunction "NIRQ_11") (pintype "bidirectional"))
    )
    (net (code "91") (name "unconnected-(U12-TX-Pad4)") (class "Default")
      (node (ref "U12") (pin "4") (pinfunction "TX_4") (pintype "output"))
    )
    (net (code "92") (name "unconnected-(U12-TXRAMP-Pad7)") (class "Default")
      (node (ref "U12") (pin "7") (pinfunction "TXRAMP_7") (pintype "bidirectional"))
    )
  )
)
